# UFBmod_1V1.net
KiCad netlist of a schematic drawn in EAGLE
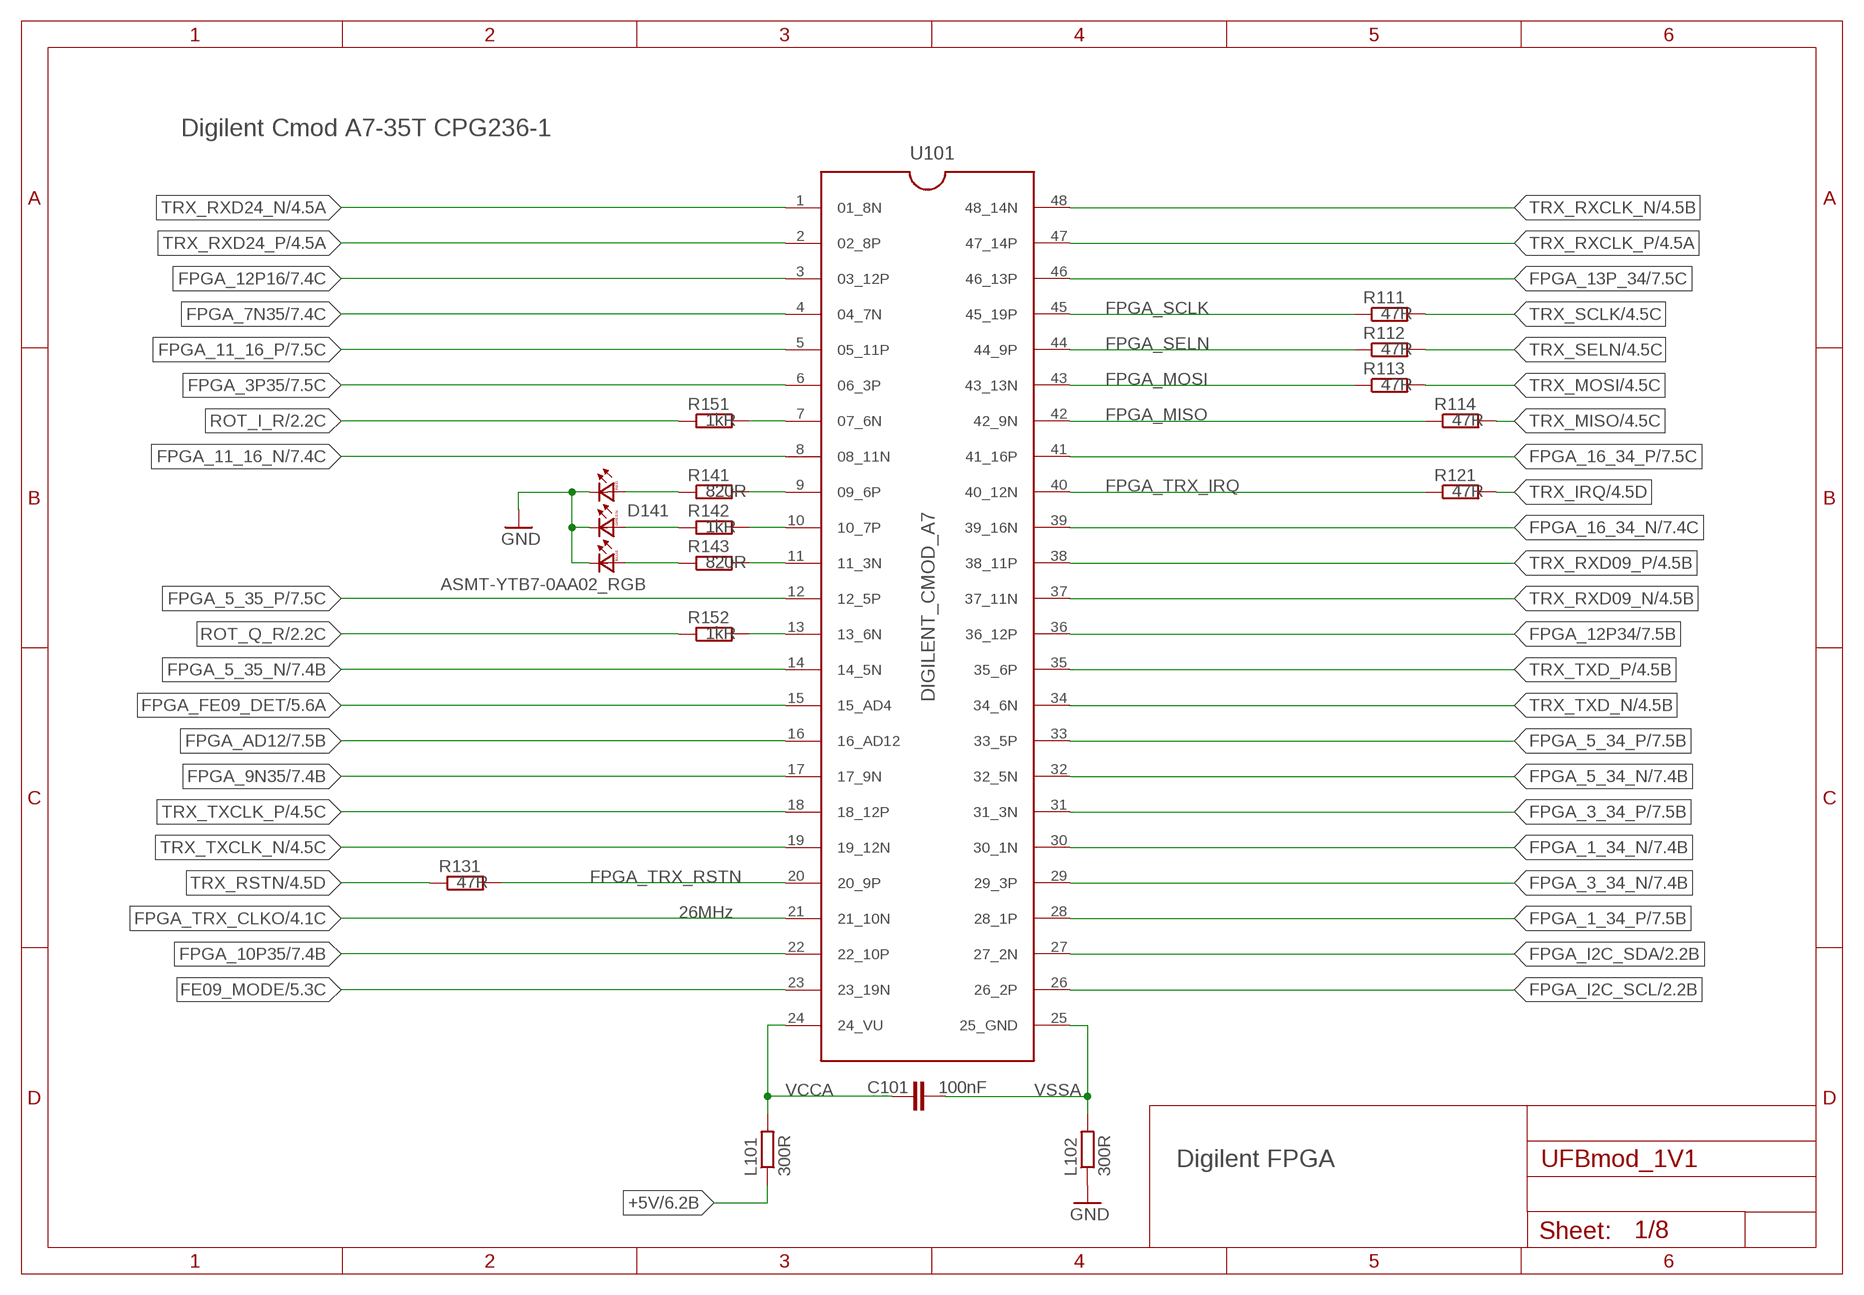
[diagram p0: schematic, sheet 1]
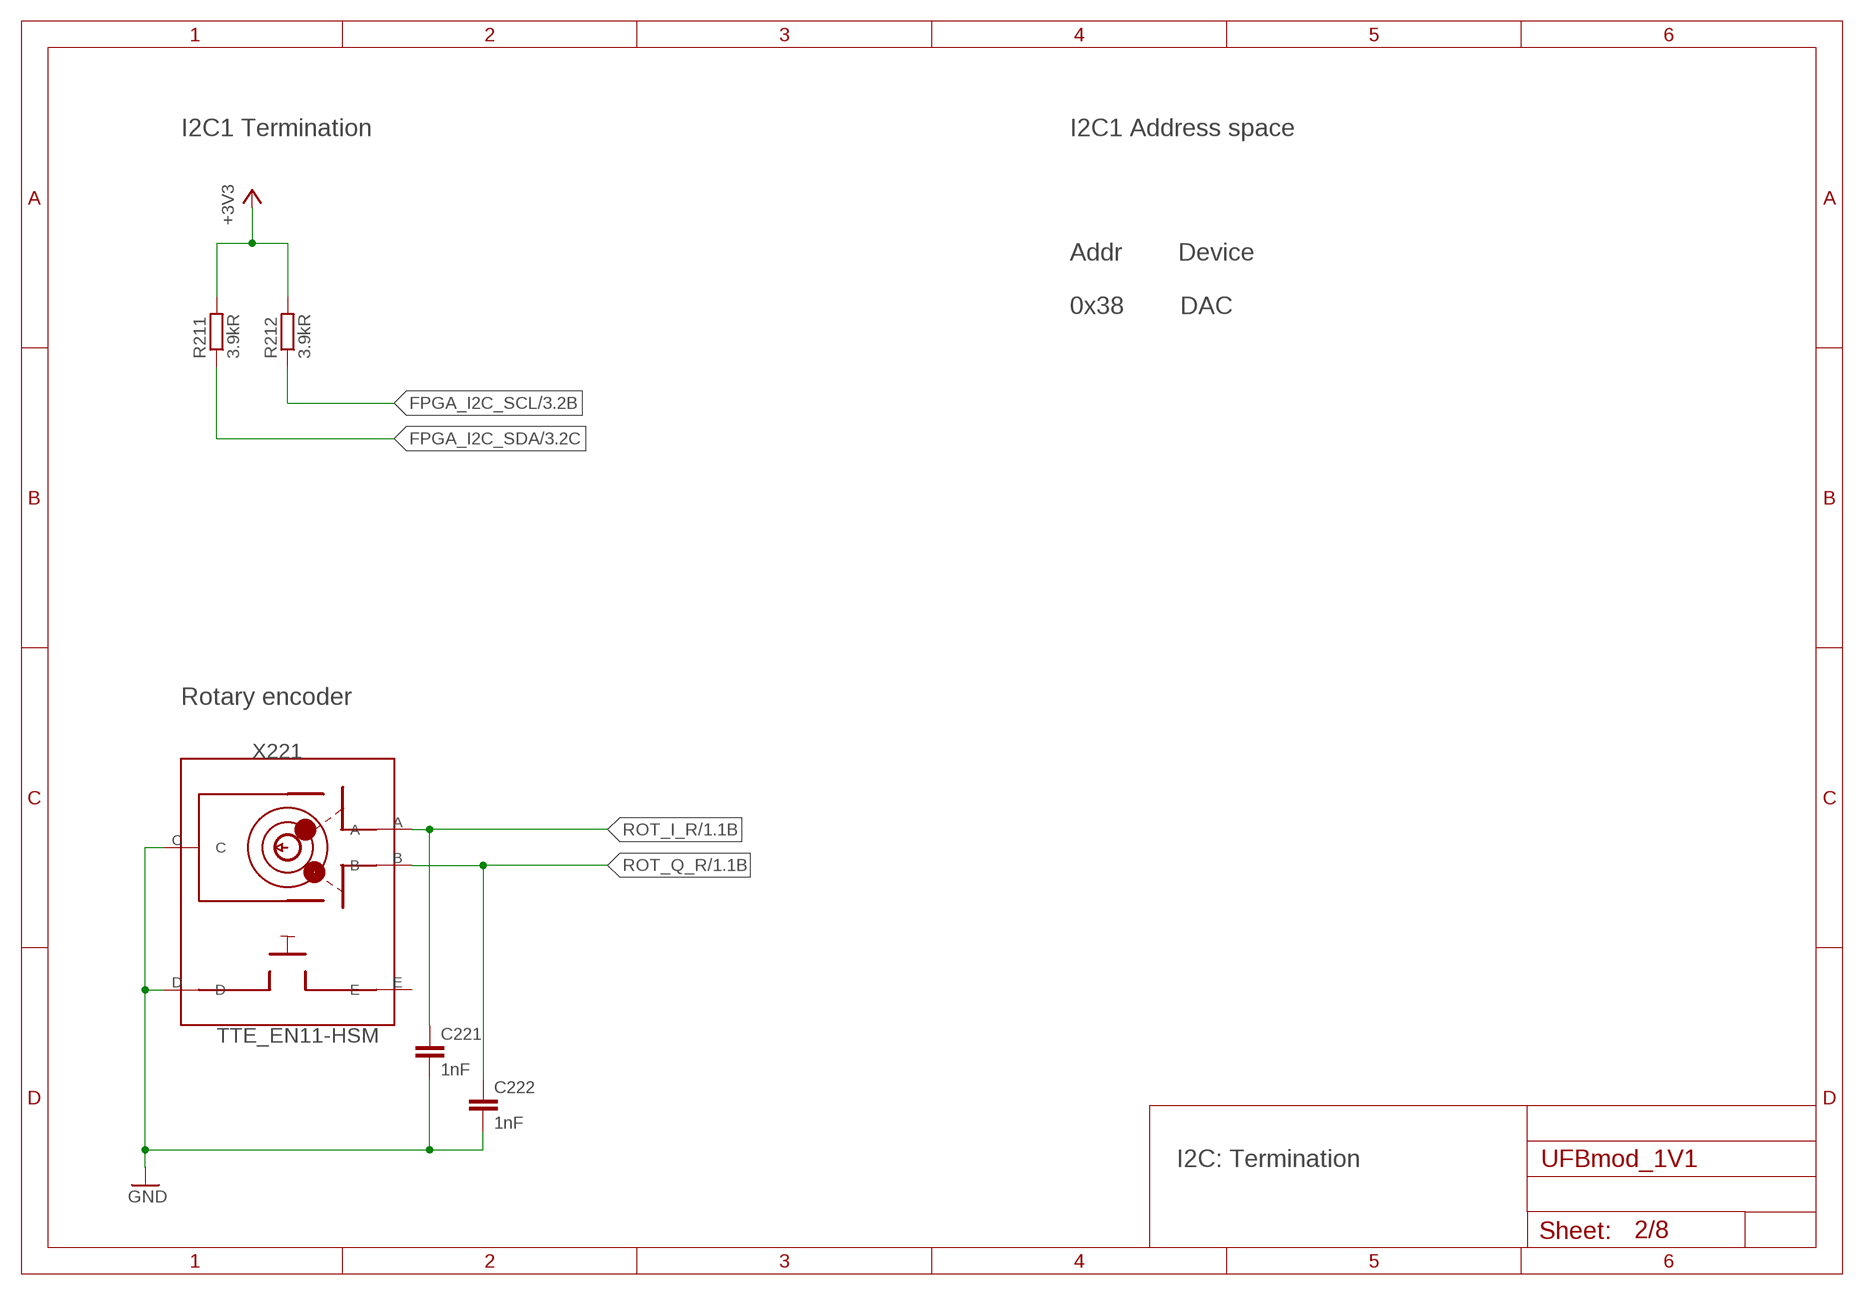
[diagram p1: schematic, sheet 2]
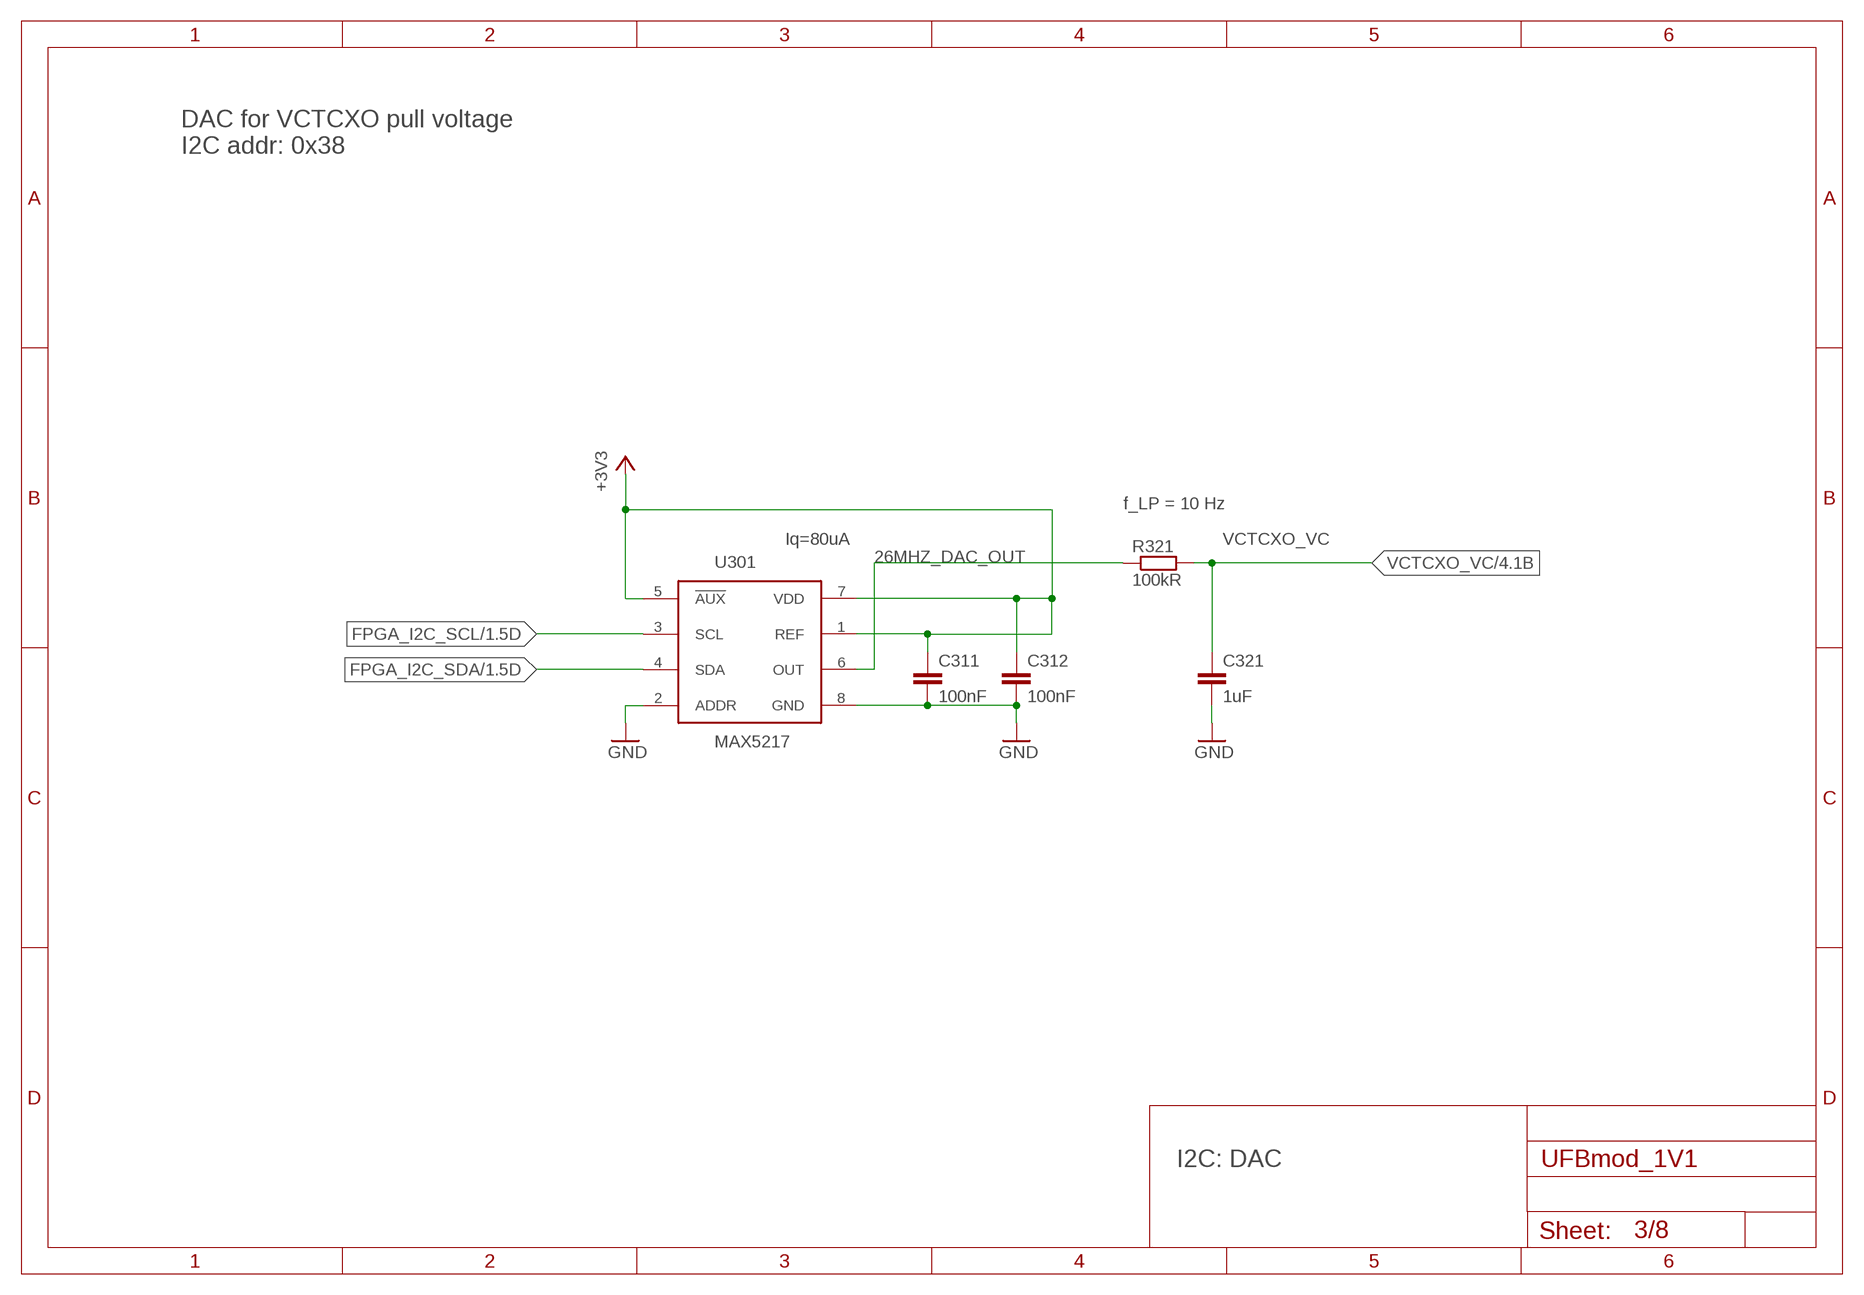
[diagram p2: schematic, sheet 3]
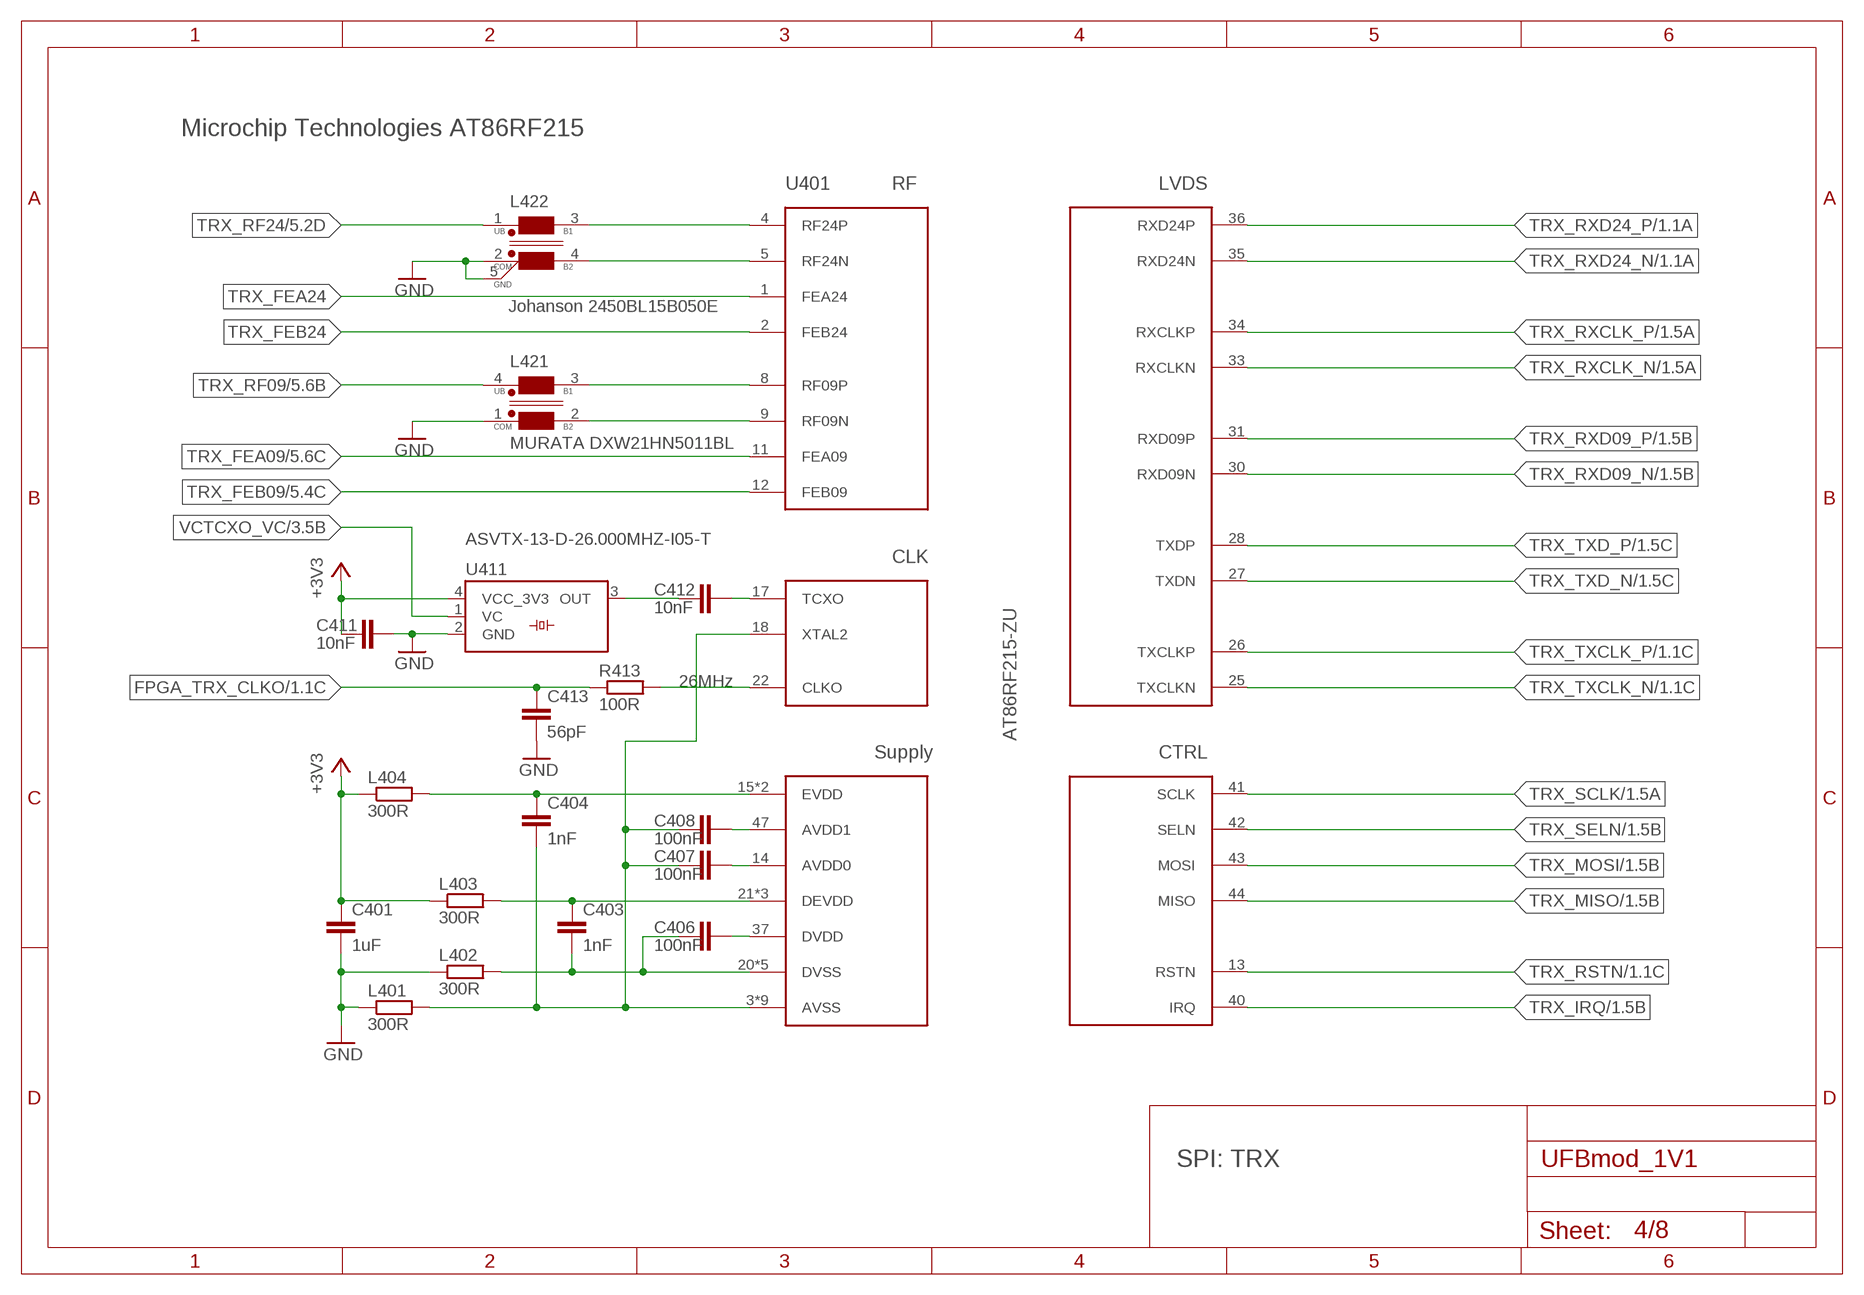
[diagram p3: schematic, sheet 4]
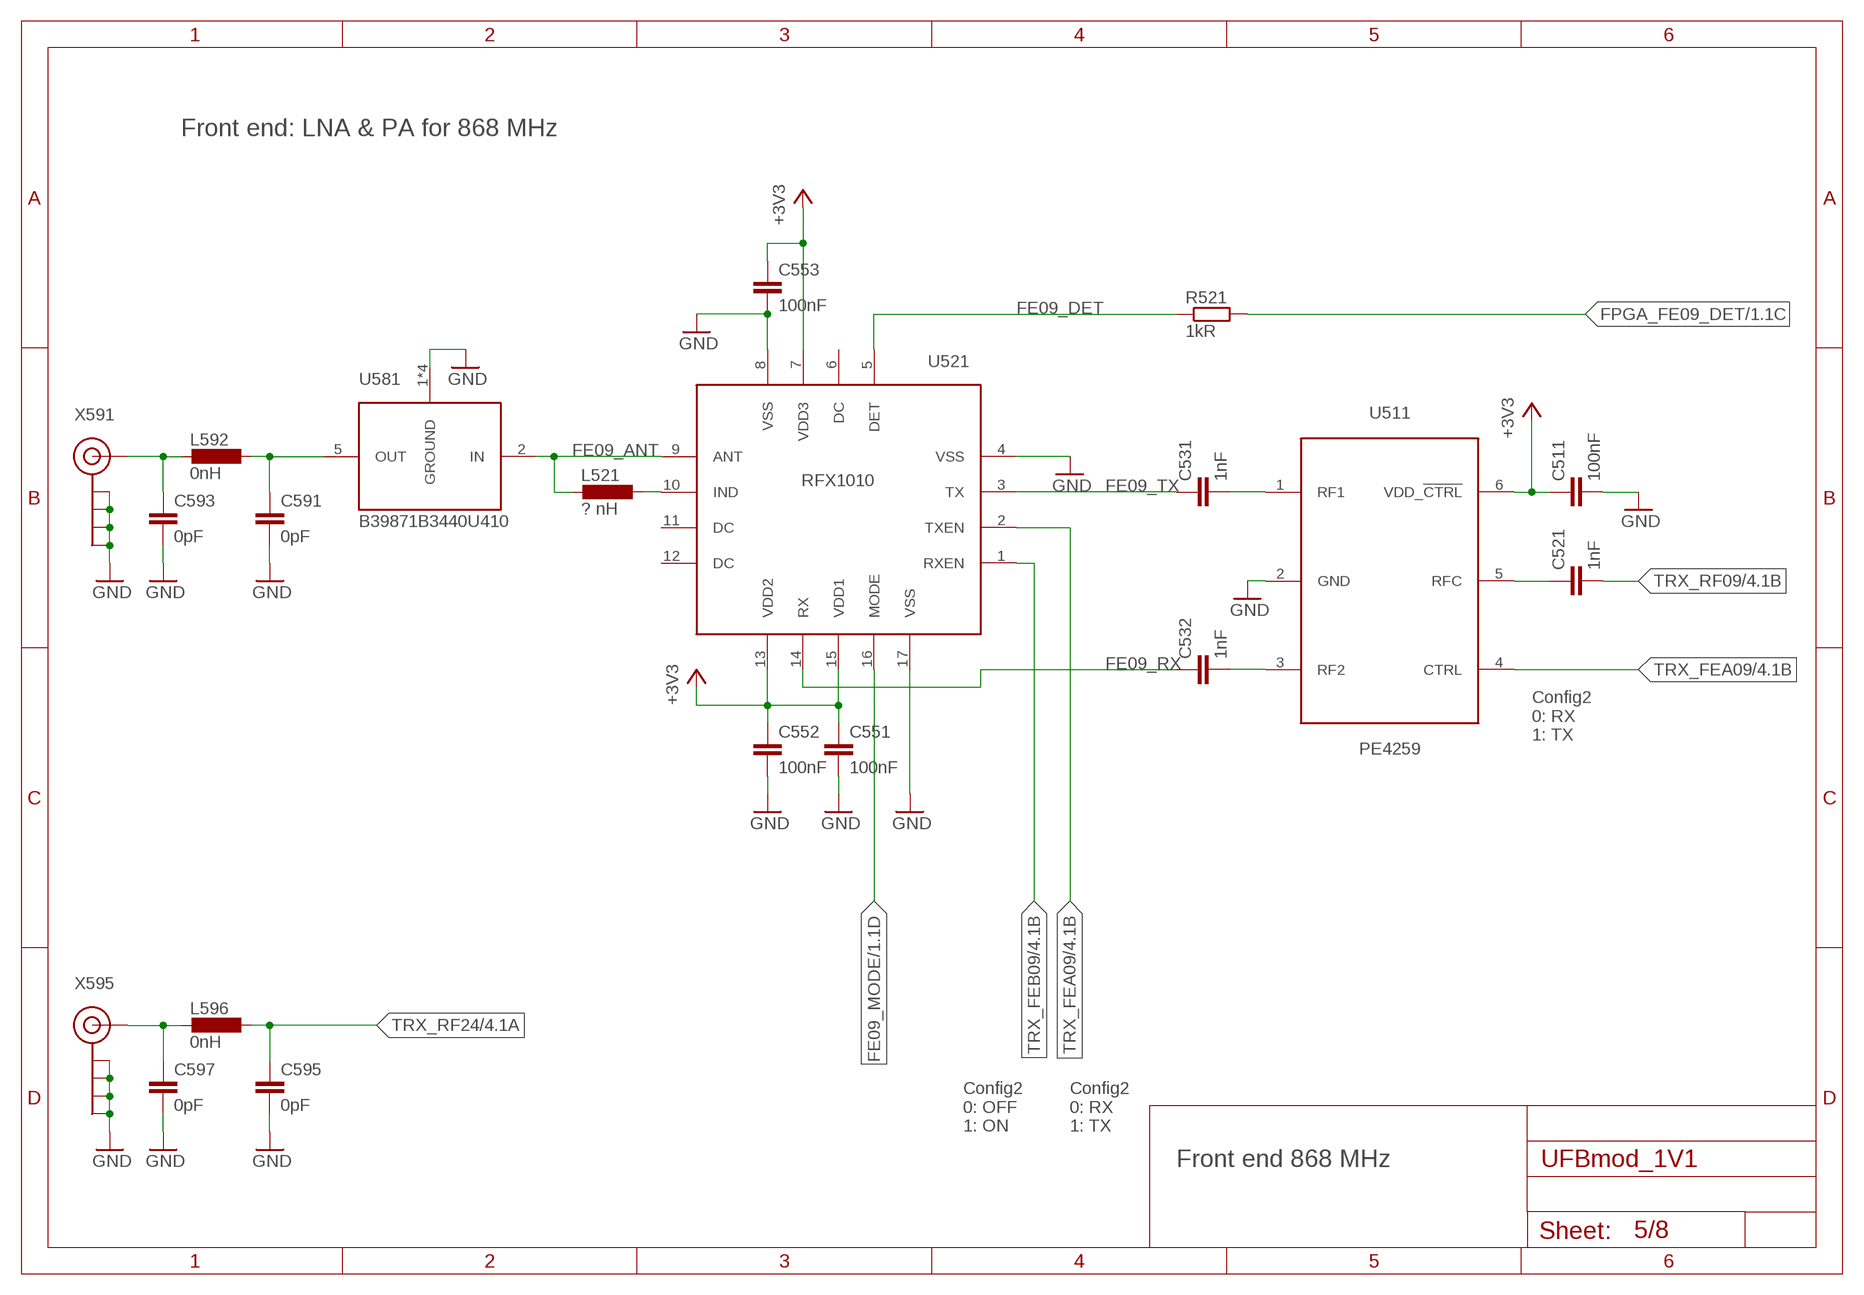
[diagram p4: schematic, sheet 5]
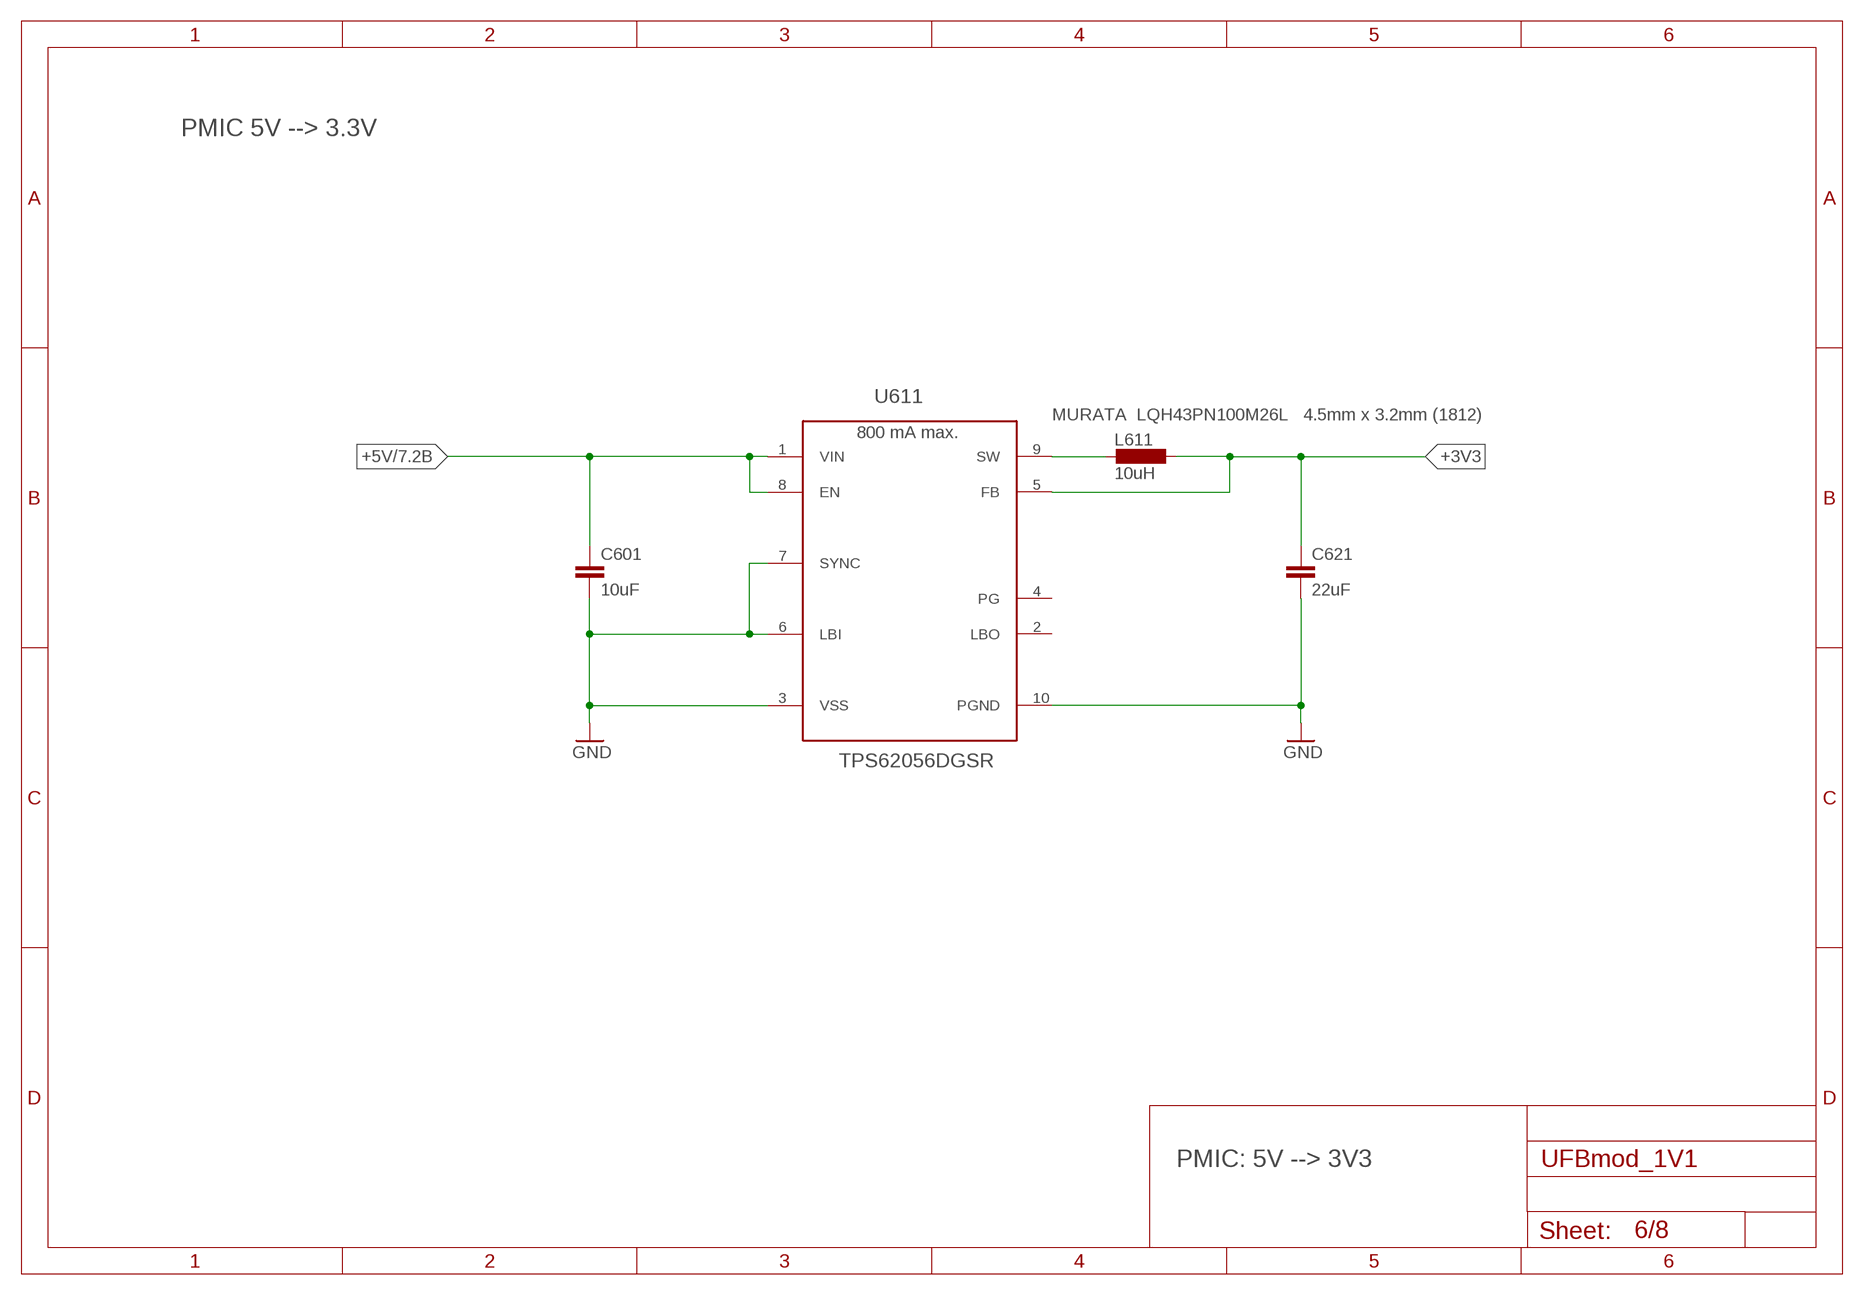
[diagram p5: schematic, sheet 6]
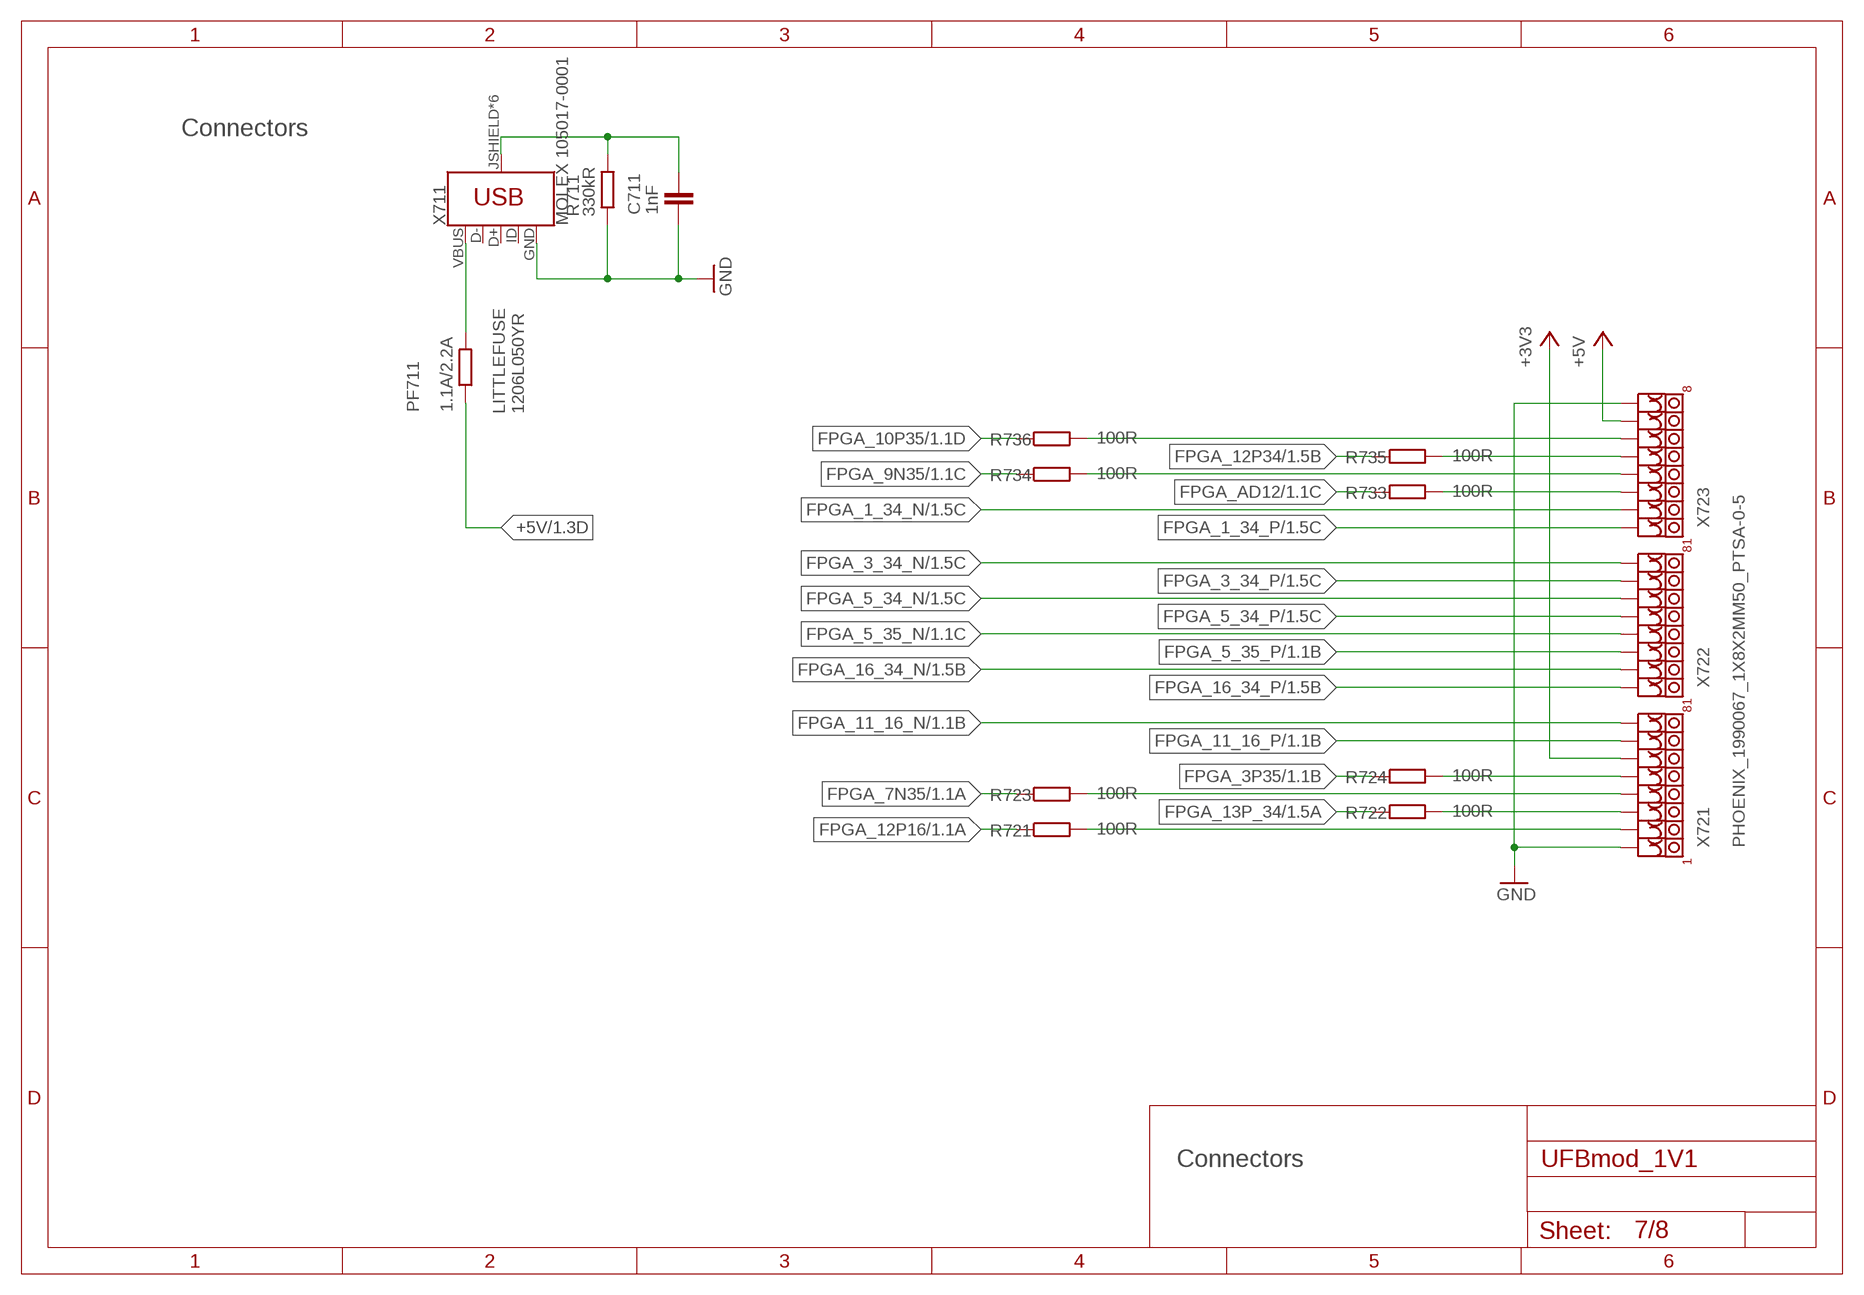
[diagram p6: schematic, sheet 7]
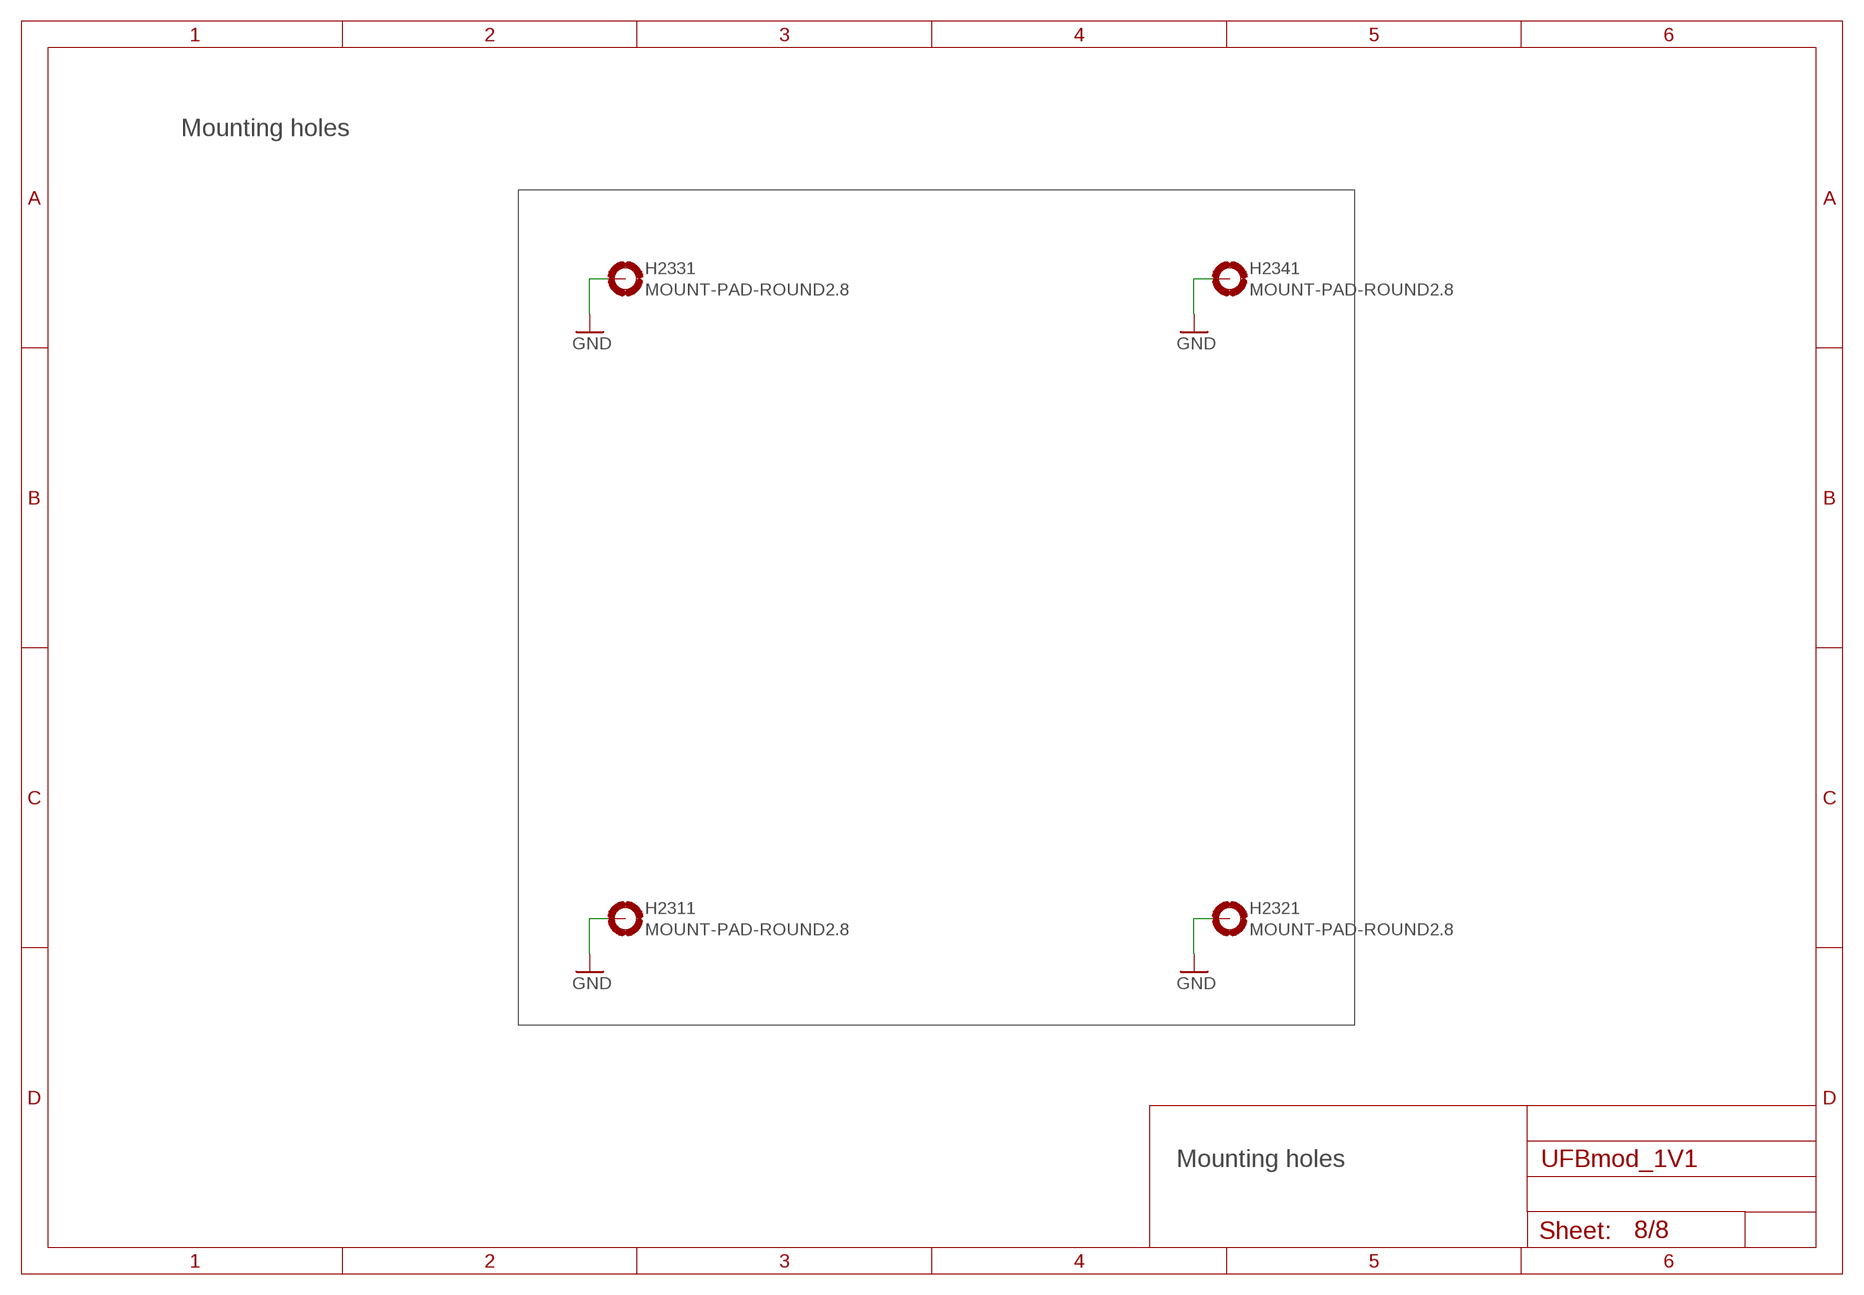
[diagram p7: schematic, sheet 8]

(export (version "E")
  (design (tool "Eeschema 10.0.6"))
  (components
    (comp (ref "C601")
      (value "10uF")
      (footprint "eagle-import:C0603")
      (libsource (lib "eagle-import") (part "C-EUC0603"))
    )
    (comp (ref "C621")
      (value "22uF")
      (footprint "eagle-import:C0603")
      (libsource (lib "eagle-import") (part "C-EUC0603"))
    )
    (comp (ref "L611")
      (value "10uH")
      (footprint "eagle-import:L1812")
      (libsource (lib "eagle-import") (part "L-EUL1812"))
    )
    (comp (ref "U611")
      (value "TPS62056DGSR")
      (footprint "eagle-import:S-PDSO-G10")
      (libsource (lib "eagle-import") (part "TPS62051"))
    )
    (comp (ref "C711")
      (value "1nF")
      (footprint "eagle-import:C0402")
      (libsource (lib "eagle-import") (part "C-EUC0402"))
    )
    (comp (ref "PF711")
      (value "1.1A/2.2A")
      (footprint "eagle-import:M1206")
      (libsource (lib "eagle-import") (part "rcl_R-EU_M1206"))
    )
    (comp (ref "R711")
      (value "330kR")
      (footprint "eagle-import:R0402")
      (libsource (lib "eagle-import") (part "R-EU_R0402"))
    )
    (comp (ref "R721")
      (value "100R")
      (footprint "eagle-import:R0402")
      (libsource (lib "eagle-import") (part "R-EU_R0402"))
    )
    (comp (ref "R722")
      (value "100R")
      (footprint "eagle-import:R0402")
      (libsource (lib "eagle-import") (part "R-EU_R0402"))
    )
    (comp (ref "R723")
      (value "100R")
      (footprint "eagle-import:R0402")
      (libsource (lib "eagle-import") (part "R-EU_R0402"))
    )
    (comp (ref "R724")
      (value "100R")
      (footprint "eagle-import:R0402")
      (libsource (lib "eagle-import") (part "R-EU_R0402"))
    )
    (comp (ref "R733")
      (value "100R")
      (footprint "eagle-import:R0402")
      (libsource (lib "eagle-import") (part "R-EU_R0402"))
    )
    (comp (ref "R734")
      (value "100R")
      (footprint "eagle-import:R0402")
      (libsource (lib "eagle-import") (part "R-EU_R0402"))
    )
    (comp (ref "R735")
      (value "100R")
      (footprint "eagle-import:R0402")
      (libsource (lib "eagle-import") (part "R-EU_R0402"))
    )
    (comp (ref "R736")
      (value "100R")
      (footprint "eagle-import:R0402")
      (libsource (lib "eagle-import") (part "R-EU_R0402"))
    )
    (comp (ref "X711")
      (value "MOLEX 105017-0001")
      (footprint "eagle-import:USB-B-MICRO-SMD_MOLEX-105017-0001")
      (libsource (lib "eagle-import") (part "USB_MICRO-B_MOLEX"))
    )
    (comp (ref "X721")
      (value "PHOENIX_1990067_1X8X2MM50_PTSA-0-5")
      (footprint "eagle-import:PHOENIX_1990067_1X8X2MM50_PTSA-0-5")
      (libsource (lib "eagle-import") (part "PHOENIX_1990067_1X8X2MM50_PTSA-0-5"))
    )
    (comp (ref "X722")
      (value "PHOENIX_1990067_1X8X2MM50_PTSA-0-5")
      (footprint "eagle-import:PHOENIX_1990067_1X8X2MM50_PTSA-0-5")
      (libsource (lib "eagle-import") (part "PHOENIX_1990067_1X8X2MM50_PTSA-0-5"))
    )
    (comp (ref "X723")
      (value "PHOENIX_1990067_1X8X2MM50_PTSA-0-5")
      (footprint "eagle-import:PHOENIX_1990067_1X8X2MM50_PTSA-0-5")
      (libsource (lib "eagle-import") (part "PHOENIX_1990067_1X8X2MM50_PTSA-0-5"))
    )
    (comp (ref "C511")
      (value "100nF")
      (footprint "eagle-import:C0402")
      (libsource (lib "eagle-import") (part "C-EUC0402"))
    )
    (comp (ref "C521")
      (value "1nF")
      (footprint "eagle-import:C0402")
      (libsource (lib "eagle-import") (part "C-EUC0402"))
    )
    (comp (ref "C531")
      (value "1nF")
      (footprint "eagle-import:C0402")
      (libsource (lib "eagle-import") (part "C-EUC0402"))
    )
    (comp (ref "C532")
      (value "1nF")
      (footprint "eagle-import:C0402")
      (libsource (lib "eagle-import") (part "C-EUC0402"))
    )
    (comp (ref "C551")
      (value "100nF")
      (footprint "eagle-import:C0402")
      (libsource (lib "eagle-import") (part "C-EUC0402"))
    )
    (comp (ref "C552")
      (value "100nF")
      (footprint "eagle-import:C0402")
      (libsource (lib "eagle-import") (part "C-EUC0402"))
    )
    (comp (ref "C553")
      (value "100nF")
      (footprint "eagle-import:C0402")
      (libsource (lib "eagle-import") (part "C-EUC0402"))
    )
    (comp (ref "C591")
      (value "0pF")
      (footprint "eagle-import:C0402")
      (libsource (lib "eagle-import") (part "C-EUC0402"))
    )
    (comp (ref "C593")
      (value "0pF")
      (footprint "eagle-import:C0402")
      (libsource (lib "eagle-import") (part "C-EUC0402"))
    )
    (comp (ref "C595")
      (value "0pF")
      (footprint "eagle-import:C0402")
      (libsource (lib "eagle-import") (part "C-EUC0402"))
    )
    (comp (ref "C597")
      (value "0pF")
      (footprint "eagle-import:C0402")
      (libsource (lib "eagle-import") (part "C-EUC0402"))
    )
    (comp (ref "L521")
      (value "? nH")
      (footprint "eagle-import:L0603")
      (libsource (lib "eagle-import") (part "L-EUL0603"))
    )
    (comp (ref "L592")
      (value "0nH")
      (footprint "eagle-import:L0603")
      (libsource (lib "eagle-import") (part "L-EUL0603"))
    )
    (comp (ref "L596")
      (value "0nH")
      (footprint "eagle-import:L0603")
      (libsource (lib "eagle-import") (part "L-EUL0603"))
    )
    (comp (ref "R521")
      (value "1kR")
      (footprint "eagle-import:R0402")
      (libsource (lib "eagle-import") (part "R-EU_R0402"))
    )
    (comp (ref "U511")
      (value "PE4259")
      (footprint "eagle-import:SC-70_6-LEAD_2X1MM25_0P65")
      (libsource (lib "eagle-import") (part "PE4259"))
    )
    (comp (ref "U521")
      (value "RFX1010")
      (footprint "eagle-import:QFN16-3X3-0P5-PAD")
      (libsource (lib "eagle-import") (part "RFX1010"))
    )
    (comp (ref "U581")
      (value "B39871B3440U410")
      (footprint "eagle-import:B3440_3MM-X-3MM")
      (libsource (lib "eagle-import") (part "B3440"))
    )
    (comp (ref "X591")
      (value "ANTENNATINY")
      (footprint "eagle-import:SMA_UFL_PAD_TINY")
      (libsource (lib "eagle-import") (part "ANTENNATINY"))
    )
    (comp (ref "X595")
      (value "ANTENNATINY")
      (footprint "eagle-import:SMA_UFL_PAD_TINY")
      (libsource (lib "eagle-import") (part "ANTENNATINY"))
    )
    (comp (ref "C311")
      (value "100nF")
      (footprint "eagle-import:C0402")
      (libsource (lib "eagle-import") (part "C-EUC0402"))
    )
    (comp (ref "C312")
      (value "100nF")
      (footprint "eagle-import:C0402")
      (libsource (lib "eagle-import") (part "C-EUC0402"))
    )
    (comp (ref "C321")
      (value "1uF")
      (footprint "eagle-import:C0402")
      (libsource (lib "eagle-import") (part "C-EUC0402"))
    )
    (comp (ref "R321")
      (value "100kR")
      (footprint "eagle-import:R0402")
      (libsource (lib "eagle-import") (part "R-EU_R0402"))
    )
    (comp (ref "U301")
      (value "MAX5217")
      (footprint "eagle-import:µMAX8")
      (libsource (lib "eagle-import") (part "MAX5217"))
    )
    (comp (ref "H2311")
      (value "MOUNT-PAD-ROUND2.8")
      (footprint "eagle-import:2,8-PAD")
      (libsource (lib "eagle-import") (part "MOUNT-PAD-ROUND2.8"))
    )
    (comp (ref "H2321")
      (value "MOUNT-PAD-ROUND2.8")
      (footprint "eagle-import:2,8-PAD")
      (libsource (lib "eagle-import") (part "MOUNT-PAD-ROUND2.8"))
    )
    (comp (ref "H2331")
      (value "MOUNT-PAD-ROUND2.8")
      (footprint "eagle-import:2,8-PAD")
      (libsource (lib "eagle-import") (part "MOUNT-PAD-ROUND2.8"))
    )
    (comp (ref "H2341")
      (value "MOUNT-PAD-ROUND2.8")
      (footprint "eagle-import:2,8-PAD")
      (libsource (lib "eagle-import") (part "MOUNT-PAD-ROUND2.8"))
    )
    (comp (ref "C401")
      (value "1uF")
      (footprint "eagle-import:C0402")
      (libsource (lib "eagle-import") (part "C-EUC0402"))
    )
    (comp (ref "C403")
      (value "1nF")
      (footprint "eagle-import:C0402")
      (libsource (lib "eagle-import") (part "C-EUC0402"))
    )
    (comp (ref "C404")
      (value "1nF")
      (footprint "eagle-import:C0402")
      (libsource (lib "eagle-import") (part "C-EUC0402"))
    )
    (comp (ref "C406")
      (value "100nF")
      (footprint "eagle-import:C0402")
      (libsource (lib "eagle-import") (part "C-EUC0402"))
    )
    (comp (ref "C407")
      (value "100nF")
      (footprint "eagle-import:C0402")
      (libsource (lib "eagle-import") (part "C-EUC0402"))
    )
    (comp (ref "C408")
      (value "100nF")
      (footprint "eagle-import:C0402")
      (libsource (lib "eagle-import") (part "C-EUC0402"))
    )
    (comp (ref "C411")
      (value "10nF")
      (footprint "eagle-import:C0402")
      (libsource (lib "eagle-import") (part "C-EUC0402"))
    )
    (comp (ref "C412")
      (value "10nF")
      (footprint "eagle-import:C0402")
      (libsource (lib "eagle-import") (part "C-EUC0402"))
    )
    (comp (ref "C413")
      (value "56pF")
      (footprint "eagle-import:C0402")
      (libsource (lib "eagle-import") (part "C-EUC0402"))
    )
    (comp (ref "L401")
      (value "300R")
      (footprint "eagle-import:R1206")
      (libsource (lib "eagle-import") (part "R-EU_R1206"))
    )
    (comp (ref "L402")
      (value "300R")
      (footprint "eagle-import:R1206")
      (libsource (lib "eagle-import") (part "R-EU_R1206"))
    )
    (comp (ref "L403")
      (value "300R")
      (footprint "eagle-import:R1206")
      (libsource (lib "eagle-import") (part "R-EU_R1206"))
    )
    (comp (ref "L404")
      (value "300R")
      (footprint "eagle-import:R1206")
      (libsource (lib "eagle-import") (part "R-EU_R1206"))
    )
    (comp (ref "L421")
      (value "MURATA DXW21HN5011BL")
      (footprint "eagle-import:DXW21HN5011BL")
      (libsource (lib "eagle-import") (part "DXW21HN5011BL"))
    )
    (comp (ref "L422")
      (value "Johanson 2450BL15B050E")
      (footprint "eagle-import:2450BL15B050")
      (libsource (lib "eagle-import") (part "2450BL15B050"))
    )
    (comp (ref "R413")
      (value "100R")
      (footprint "eagle-import:R0402")
      (libsource (lib "eagle-import") (part "R-EU_R0402"))
    )
    (comp (ref "U401")
      (value "AT86RF215-ZU")
      (footprint "eagle-import:QFN48_7X7-0P5-PAD")
      (libsource (lib "eagle-import") (part "AT86RF215"))
    )
    (comp (ref "U411")
      (value "ASVTX-13-D-26.000MHZ-I05-T")
      (footprint "eagle-import:ASVTX-13")
      (libsource (lib "eagle-import") (part "ASVTX-13-D"))
    )
    (comp (ref "C101")
      (value "100nF")
      (footprint "eagle-import:C0402")
      (libsource (lib "eagle-import") (part "C-EUC0402"))
    )
    (comp (ref "D141")
      (value "ASMT-YTB7-0AA02_RGB")
      (footprint "eagle-import:ASMT-YTB7_0AA02_RGB")
      (libsource (lib "eagle-import") (part "ASMT-YTB7-0AA02_RGB"))
    )
    (comp (ref "L101")
      (value "300R")
      (footprint "eagle-import:R1206")
      (libsource (lib "eagle-import") (part "R-EU_R1206"))
    )
    (comp (ref "L102")
      (value "300R")
      (footprint "eagle-import:R1206")
      (libsource (lib "eagle-import") (part "R-EU_R1206"))
    )
    (comp (ref "R111")
      (value "47R")
      (footprint "eagle-import:R0402")
      (libsource (lib "eagle-import") (part "R-EU_R0402"))
    )
    (comp (ref "R112")
      (value "47R")
      (footprint "eagle-import:R0402")
      (libsource (lib "eagle-import") (part "R-EU_R0402"))
    )
    (comp (ref "R113")
      (value "47R")
      (footprint "eagle-import:R0402")
      (libsource (lib "eagle-import") (part "R-EU_R0402"))
    )
    (comp (ref "R114")
      (value "47R")
      (footprint "eagle-import:R0402")
      (libsource (lib "eagle-import") (part "R-EU_R0402"))
    )
    (comp (ref "R121")
      (value "47R")
      (footprint "eagle-import:R0402")
      (libsource (lib "eagle-import") (part "R-EU_R0402"))
    )
    (comp (ref "R131")
      (value "47R")
      (footprint "eagle-import:R0402")
      (libsource (lib "eagle-import") (part "R-EU_R0402"))
    )
    (comp (ref "R141")
      (value "820R")
      (footprint "eagle-import:R0402")
      (libsource (lib "eagle-import") (part "R-EU_R0402"))
    )
    (comp (ref "R142")
      (value "1kR")
      (footprint "eagle-import:R0402")
      (libsource (lib "eagle-import") (part "R-EU_R0402"))
    )
    (comp (ref "R143")
      (value "820R")
      (footprint "eagle-import:R0402")
      (libsource (lib "eagle-import") (part "R-EU_R0402"))
    )
    (comp (ref "R151")
      (value "1kR")
      (footprint "eagle-import:R0402")
      (libsource (lib "eagle-import") (part "R-EU_R0402"))
    )
    (comp (ref "R152")
      (value "1kR")
      (footprint "eagle-import:R0402")
      (libsource (lib "eagle-import") (part "R-EU_R0402"))
    )
    (comp (ref "U101")
      (value "DIGILENT_CMOD_A7")
      (footprint "eagle-import:DIGILENT_CMOD_A7__DIP48")
      (libsource (lib "eagle-import") (part "DIGILENT_CMOD_A7"))
    )
    (comp (ref "C221")
      (value "1nF")
      (footprint "eagle-import:C0402")
      (libsource (lib "eagle-import") (part "C-EUC0402"))
    )
    (comp (ref "C222")
      (value "1nF")
      (footprint "eagle-import:C0402")
      (libsource (lib "eagle-import") (part "C-EUC0402"))
    )
    (comp (ref "R211")
      (value "3.9kR")
      (footprint "eagle-import:R0402")
      (libsource (lib "eagle-import") (part "R-EU_R0402"))
    )
    (comp (ref "R212")
      (value "3.9kR")
      (footprint "eagle-import:R0402")
      (libsource (lib "eagle-import") (part "R-EU_R0402"))
    )
    (comp (ref "X221")
      (value "TTE_EN11-HSM")
      (footprint "eagle-import:TTE_EN11-HSM")
      (libsource (lib "eagle-import") (part "TTE_EN11-HSM"))
    )
  )
  (nets
    (net (code "1") (name "+3V3") (class "Default")
      (node (ref "C311") (pin "1") (pinfunction "1_1") (pintype "passive"))
      (node (ref "C312") (pin "1") (pinfunction "1_1") (pintype "passive"))
      (node (ref "C401") (pin "1") (pinfunction "1_1") (pintype "passive"))
      (node (ref "C411") (pin "1") (pinfunction "1_1") (pintype "passive"))
      (node (ref "C511") (pin "1") (pinfunction "1_1") (pintype "passive"))
      (node (ref "C551") (pin "1") (pinfunction "1_1") (pintype "passive"))
      (node (ref "C552") (pin "1") (pinfunction "1_1") (pintype "passive"))
      (node (ref "C553") (pin "1") (pinfunction "1_1") (pintype "passive"))
      (node (ref "C621") (pin "1") (pinfunction "1_1") (pintype "passive"))
      (node (ref "L403") (pin "1") (pinfunction "1_1") (pintype "passive"))
      (node (ref "L404") (pin "1") (pinfunction "1_1") (pintype "passive"))
      (node (ref "L611") (pin "1") (pinfunction "1_1") (pintype "passive"))
      (node (ref "R211") (pin "2") (pinfunction "2_2") (pintype "passive"))
      (node (ref "R212") (pin "2") (pinfunction "2_2") (pintype "passive"))
      (node (ref "U301") (pin "1") (pinfunction "REF_1") (pintype "passive"))
      (node (ref "U301") (pin "5") (pinfunction "~{AUX}_5") (pintype "input"))
      (node (ref "U301") (pin "7") (pinfunction "VDD_7") (pintype "power_in"))
      (node (ref "U411") (pin "4") (pinfunction "VCC_3V3_4") (pintype "power_in"))
      (node (ref "U511") (pin "6") (pinfunction "VDD_~{CTRL}_6") (pintype "passive"))
      (node (ref "U521") (pin "13") (pinfunction "VDD2_13") (pintype "power_in"))
      (node (ref "U521") (pin "15") (pinfunction "VDD1_15") (pintype "power_in"))
      (node (ref "U521") (pin "7") (pinfunction "VDD3_7") (pintype "power_in"))
      (node (ref "U611") (pin "5") (pinfunction "FB_5") (pintype "passive"))
      (node (ref "X721") (pin "6") (pinfunction "6_6") (pintype "passive"))
    )
    (net (code "2") (name "+5V") (class "Default")
      (node (ref "C601") (pin "1") (pinfunction "1_1") (pintype "passive"))
      (node (ref "L101") (pin "1") (pinfunction "1_1") (pintype "passive"))
      (node (ref "PF711") (pin "1") (pinfunction "1_1") (pintype "passive"))
      (node (ref "U611") (pin "1") (pinfunction "VIN_1") (pintype "power_in"))
      (node (ref "U611") (pin "8") (pinfunction "EN_8") (pintype "input"))
      (node (ref "X723") (pin "7") (pinfunction "7_7") (pintype "passive"))
    )
    (net (code "3") (name "26MHZ_DAC_OUT") (class "Default")
      (node (ref "R321") (pin "1") (pinfunction "1_1") (pintype "passive"))
      (node (ref "U301") (pin "6") (pinfunction "OUT_6") (pintype "passive"))
    )
    (net (code "4") (name "FE09_ANT") (class "Default")
      (node (ref "L521") (pin "2") (pinfunction "2_2") (pintype "passive"))
      (node (ref "U521") (pin "9") (pinfunction "ANT_9") (pintype "bidirectional"))
      (node (ref "U581") (pin "2") (pinfunction "IN_2") (pintype "passive"))
    )
    (net (code "5") (name "FE09_DET") (class "Default")
      (node (ref "R521") (pin "1") (pinfunction "1_1") (pintype "passive"))
      (node (ref "U521") (pin "5") (pinfunction "DET_5") (pintype "output"))
    )
    (net (code "6") (name "FE09_MODE") (class "Default")
      (node (ref "U101") (pin "23") (pinfunction "23_19N_23") (pintype "bidirectional"))
      (node (ref "U521") (pin "16") (pinfunction "MODE_16") (pintype "input"))
    )
    (net (code "7") (name "FE09_RX") (class "Default")
      (node (ref "C532") (pin "1") (pinfunction "1_1") (pintype "passive"))
      (node (ref "U521") (pin "14") (pinfunction "RX_14") (pintype "output"))
    )
    (net (code "8") (name "FE09_TX") (class "Default")
      (node (ref "C531") (pin "1") (pinfunction "1_1") (pintype "passive"))
      (node (ref "U521") (pin "3") (pinfunction "TX_3") (pintype "input"))
    )
    (net (code "9") (name "FPGA_1_34_N") (class "Default")
      (node (ref "U101") (pin "30") (pinfunction "30_1N_30") (pintype "bidirectional"))
      (node (ref "X723") (pin "2") (pinfunction "2_2") (pintype "passive"))
    )
    (net (code "10") (name "FPGA_1_34_P") (class "Default")
      (node (ref "U101") (pin "28") (pinfunction "28_1P_28") (pintype "bidirectional"))
      (node (ref "X723") (pin "1") (pinfunction "1_1") (pintype "passive"))
    )
    (net (code "11") (name "FPGA_3P35") (class "Default")
      (node (ref "R724") (pin "1") (pinfunction "1_1") (pintype "passive"))
      (node (ref "U101") (pin "6") (pinfunction "06_3P_6") (pintype "bidirectional"))
    )
    (net (code "12") (name "FPGA_3_34_N") (class "Default")
      (node (ref "U101") (pin "29") (pinfunction "29_3P_29") (pintype "bidirectional"))
      (node (ref "X722") (pin "8") (pinfunction "8_8") (pintype "passive"))
    )
    (net (code "13") (name "FPGA_3_34_P") (class "Default")
      (node (ref "U101") (pin "31") (pinfunction "31_3N_31") (pintype "bidirectional"))
      (node (ref "X722") (pin "7") (pinfunction "7_7") (pintype "passive"))
    )
    (net (code "14") (name "FPGA_5_34_N") (class "Default")
      (node (ref "U101") (pin "32") (pinfunction "32_5N_32") (pintype "bidirectional"))
      (node (ref "X722") (pin "6") (pinfunction "6_6") (pintype "passive"))
    )
    (net (code "15") (name "FPGA_5_34_P") (class "Default")
      (node (ref "U101") (pin "33") (pinfunction "33_5P_33") (pintype "bidirectional"))
      (node (ref "X722") (pin "5") (pinfunction "5_5") (pintype "passive"))
    )
    (net (code "16") (name "FPGA_5_35_N") (class "Default")
      (node (ref "U101") (pin "14") (pinfunction "14_5N_14") (pintype "bidirectional"))
      (node (ref "X722") (pin "4") (pinfunction "4_4") (pintype "passive"))
    )
    (net (code "17") (name "FPGA_5_35_P") (class "Default")
      (node (ref "U101") (pin "12") (pinfunction "12_5P_12") (pintype "bidirectional"))
      (node (ref "X722") (pin "3") (pinfunction "3_3") (pintype "passive"))
    )
    (net (code "18") (name "FPGA_7N35") (class "Default")
      (node (ref "R723") (pin "1") (pinfunction "1_1") (pintype "passive"))
      (node (ref "U101") (pin "4") (pinfunction "04_7N_4") (pintype "bidirectional"))
    )
    (net (code "19") (name "FPGA_9N35") (class "Default")
      (node (ref "R734") (pin "1") (pinfunction "1_1") (pintype "passive"))
      (node (ref "U101") (pin "17") (pinfunction "17_9N_17") (pintype "bidirectional"))
    )
    (net (code "20") (name "FPGA_10P35") (class "Default")
      (node (ref "R736") (pin "1") (pinfunction "1_1") (pintype "passive"))
      (node (ref "U101") (pin "22") (pinfunction "22_10P_22") (pintype "bidirectional"))
    )
    (net (code "21") (name "FPGA_11_16_N") (class "Default")
      (node (ref "U101") (pin "8") (pinfunction "08_11N_8") (pintype "bidirectional"))
      (node (ref "X721") (pin "8") (pinfunction "8_8") (pintype "passive"))
    )
    (net (code "22") (name "FPGA_11_16_P") (class "Default")
      (node (ref "U101") (pin "5") (pinfunction "05_11P_5") (pintype "bidirectional"))
      (node (ref "X721") (pin "7") (pinfunction "7_7") (pintype "passive"))
    )
    (net (code "23") (name "FPGA_12P16") (class "Default")
      (node (ref "R721") (pin "1") (pinfunction "1_1") (pintype "passive"))
      (node (ref "U101") (pin "3") (pinfunction "03_12P_3") (pintype "bidirectional"))
    )
    (net (code "24") (name "FPGA_12P34") (class "Default")
      (node (ref "R735") (pin "1") (pinfunction "1_1") (pintype "passive"))
      (node (ref "U101") (pin "36") (pinfunction "36_12P_36") (pintype "bidirectional"))
    )
    (net (code "25") (name "FPGA_13P_34") (class "Default")
      (node (ref "R722") (pin "1") (pinfunction "1_1") (pintype "passive"))
      (node (ref "U101") (pin "46") (pinfunction "46_13P_46") (pintype "bidirectional"))
    )
    (net (code "26") (name "FPGA_16_34_N") (class "Default")
      (node (ref "U101") (pin "39") (pinfunction "39_16N_39") (pintype "bidirectional"))
      (node (ref "X722") (pin "2") (pinfunction "2_2") (pintype "passive"))
    )
    (net (code "27") (name "FPGA_16_34_P") (class "Default")
      (node (ref "U101") (pin "41") (pinfunction "41_16P_41") (pintype "bidirectional"))
      (node (ref "X722") (pin "1") (pinfunction "1_1") (pintype "passive"))
    )
    (net (code "28") (name "FPGA_AD12") (class "Default")
      (node (ref "R733") (pin "1") (pinfunction "1_1") (pintype "passive"))
      (node (ref "U101") (pin "16") (pinfunction "16_AD12_16") (pintype "bidirectional"))
    )
    (net (code "29") (name "FPGA_FE09_DET") (class "Default")
      (node (ref "R521") (pin "2") (pinfunction "2_2") (pintype "passive"))
      (node (ref "U101") (pin "15") (pinfunction "15_AD4_15") (pintype "bidirectional"))
    )
    (net (code "30") (name "FPGA_I2C_SCL") (class "Default")
      (node (ref "R212") (pin "1") (pinfunction "1_1") (pintype "passive"))
      (node (ref "U101") (pin "26") (pinfunction "26_2P_26") (pintype "bidirectional"))
      (node (ref "U301") (pin "3") (pinfunction "SCL_3") (pintype "input"))
    )
    (net (code "31") (name "FPGA_I2C_SDA") (class "Default")
      (node (ref "R211") (pin "1") (pinfunction "1_1") (pintype "passive"))
      (node (ref "U101") (pin "27") (pinfunction "27_2N_27") (pintype "bidirectional"))
      (node (ref "U301") (pin "4") (pinfunction "SDA_4") (pintype "tri_state"))
    )
    (net (code "32") (name "FPGA_MISO") (class "Default")
      (node (ref "R114") (pin "1") (pinfunction "1_1") (pintype "passive"))
      (node (ref "U101") (pin "42") (pinfunction "42_9N_42") (pintype "bidirectional"))
    )
    (net (code "33") (name "FPGA_MOSI") (class "Default")
      (node (ref "R113") (pin "1") (pinfunction "1_1") (pintype "passive"))
      (node (ref "U101") (pin "43") (pinfunction "43_13N_43") (pintype "bidirectional"))
    )
    (net (code "34") (name "FPGA_SCLK") (class "Default")
      (node (ref "R111") (pin "1") (pinfunction "1_1") (pintype "passive"))
      (node (ref "U101") (pin "45") (pinfunction "45_19P_45") (pintype "bidirectional"))
    )
    (net (code "35") (name "FPGA_SELN") (class "Default")
      (node (ref "R112") (pin "1") (pinfunction "1_1") (pintype "passive"))
      (node (ref "U101") (pin "44") (pinfunction "44_9P_44") (pintype "bidirectional"))
    )
    (net (code "36") (name "FPGA_TRX_CLKO") (class "Default")
      (node (ref "C413") (pin "1") (pinfunction "1_1") (pintype "passive"))
      (node (ref "R413") (pin "1") (pinfunction "1_1") (pintype "passive"))
      (node (ref "U101") (pin "21") (pinfunction "21_10N_21") (pintype "bidirectional"))
    )
    (net (code "37") (name "FPGA_TRX_IRQ") (class "Default")
      (node (ref "R121") (pin "1") (pinfunction "1_1") (pintype "passive"))
      (node (ref "U101") (pin "40") (pinfunction "40_12N_40") (pintype "bidirectional"))
    )
    (net (code "38") (name "FPGA_TRX_RSTN") (class "Default")
      (node (ref "R131") (pin "2") (pinfunction "2_2") (pintype "passive"))
      (node (ref "U101") (pin "20") (pinfunction "20_9P_20") (pintype "bidirectional"))
    )
    (net (code "39") (name "GND") (class "Default")
      (node (ref "C221") (pin "2") (pinfunction "2_2") (pintype "passive"))
      (node (ref "C222") (pin "2") (pinfunction "2_2") (pintype "passive"))
      (node (ref "C311") (pin "2") (pinfunction "2_2") (pintype "passive"))
      (node (ref "C312") (pin "2") (pinfunction "2_2") (pintype "passive"))
      (node (ref "C321") (pin "2") (pinfunction "2_2") (pintype "passive"))
      (node (ref "C401") (pin "2") (pinfunction "2_2") (pintype "passive"))
      (node (ref "C411") (pin "2") (pinfunction "2_2") (pintype "passive"))
      (node (ref "C413") (pin "2") (pinfunction "2_2") (pintype "passive"))
      (node (ref "C511") (pin "2") (pinfunction "2_2") (pintype "passive"))
      (node (ref "C551") (pin "2") (pinfunction "2_2") (pintype "passive"))
      (node (ref "C552") (pin "2") (pinfunction "2_2") (pintype "passive"))
      (node (ref "C553") (pin "2") (pinfunction "2_2") (pintype "passive"))
      (node (ref "C591") (pin "2") (pinfunction "2_2") (pintype "passive"))
      (node (ref "C593") (pin "2") (pinfunction "2_2") (pintype "passive"))
      (node (ref "C595") (pin "2") (pinfunction "2_2") (pintype "passive"))
      (node (ref "C597") (pin "2") (pinfunction "2_2") (pintype "passive"))
      (node (ref "C601") (pin "2") (pinfunction "2_2") (pintype "passive"))
      (node (ref "C621") (pin "2") (pinfunction "2_2") (pintype "passive"))
      (node (ref "C711") (pin "1") (pinfunction "1_1") (pintype "passive"))
      (node (ref "D141") (pin "1") (pinfunction "BC_1") (pintype "passive"))
      (node (ref "D141") (pin "2") (pinfunction "GC_2") (pintype "passive"))
      (node (ref "D141") (pin "3") (pinfunction "RC_3") (pintype "passive"))
      (node (ref "H2311") (pin "B2,8") (pinfunction "MOUNT_B2,8") (pintype "passive"))
      (node (ref "H2321") (pin "B2,8") (pinfunction "MOUNT_B2,8") (pintype "passive"))
      (node (ref "H2331") (pin "B2,8") (pinfunction "MOUNT_B2,8") (pintype "passive"))
      (node (ref "H2341") (pin "B2,8") (pinfunction "MOUNT_B2,8") (pintype "passive"))
      (node (ref "L102") (pin "1") (pinfunction "1_1") (pintype "passive"))
      (node (ref "L401") (pin "1") (pinfunction "1_1") (pintype "passive"))
      (node (ref "L402") (pin "1") (pinfunction "1_1") (pintype "passive"))
      (node (ref "L421") (pin "1") (pinfunction "COM_1") (pintype "passive"))
      (node (ref "L422") (pin "2") (pinfunction "COM_2") (pintype "passive"))
      (node (ref "L422") (pin "5") (pinfunction "G_N_D_5") (pintype "passive"))
      (node (ref "R711") (pin "1") (pinfunction "1_1") (pintype "passive"))
      (node (ref "U301") (pin "2") (pinfunction "ADDR_2") (pintype "input"))
      (node (ref "U301") (pin "8") (pinfunction "GND_8") (pintype "passive"))
      (node (ref "U411") (pin "2") (pinfunction "GND_2") (pintype "power_in"))
      (node (ref "U511") (pin "2") (pinfunction "GND_2") (pintype "power_in"))
      (node (ref "U521") (pin "17") (pinfunction "VSS_17") (pintype "passive"))
      (node (ref "U521") (pin "4") (pinfunction "VSS_4") (pintype "passive"))
      (node (ref "U521") (pin "8") (pinfunction "VSS_8") (pintype "passive"))
      (node (ref "U581") (pin "1") (pinfunction "GROUND_1") (pintype "passive"))
      (node (ref "U581") (pin "3") (pinfunction "GROUND_3") (pintype "passive"))
      (node (ref "U581") (pin "4") (pinfunction "GROUND_4") (pintype "passive"))
      (node (ref "U581") (pin "6") (pinfunction "GROUND_6") (pintype "passive"))
      (node (ref "U611") (pin "10") (pinfunction "PGND_10") (pintype "passive"))
      (node (ref "U611") (pin "3") (pinfunction "VSS_3") (pintype "passive"))
      (node (ref "U611") (pin "6") (pinfunction "LBI_6") (pintype "input"))
      (node (ref "U611") (pin "7") (pinfunction "SYNC_7") (pintype "input"))
      (node (ref "X221") (pin "C") (pinfunction "C_C") (pintype "passive"))
      (node (ref "X221") (pin "D") (pinfunction "D_D") (pintype "passive"))
      (node (ref "X591") (pin "GND1") (pinfunction "GND_GND1") (pintype "bidirectional"))
      (node (ref "X591") (pin "GND2") (pinfunction "GND_GND2") (pintype "bidirectional"))
      (node (ref "X591") (pin "GND3") (pinfunction "GND_GND3") (pintype "bidirectional"))
      (node (ref "X591") (pin "GND4") (pinfunction "GND_GND4") (pintype "bidirectional"))
      (node (ref "X595") (pin "GND1") (pinfunction "GND_GND1") (pintype "bidirectional"))
      (node (ref "X595") (pin "GND2") (pinfunction "GND_GND2") (pintype "bidirectional"))
      (node (ref "X595") (pin "GND3") (pinfunction "GND_GND3") (pintype "bidirectional"))
      (node (ref "X595") (pin "GND4") (pinfunction "GND_GND4") (pintype "bidirectional"))
      (node (ref "X711") (pin "GND") (pinfunction "GND_GND") (pintype "passive"))
      (node (ref "X721") (pin "1") (pinfunction "1_1") (pintype "passive"))
      (node (ref "X723") (pin "8") (pinfunction "8_8") (pintype "passive"))
    )
    (net (code "40") (name "Net-(C403-Pad1)") (class "Default")
      (node (ref "C403") (pin "1") (pinfunction "1_1") (pintype "passive"))
      (node (ref "L403") (pin "2") (pinfunction "2_2") (pintype "passive"))
      (node (ref "U401") (pin "21") (pinfunction "DEVDD_21") (pintype "power_in"))
      (node (ref "U401") (pin "29") (pinfunction "DEVDD_29") (pintype "power_in"))
      (node (ref "U401") (pin "39") (pinfunction "DEVDD_39") (pintype "power_in"))
    )
    (net (code "41") (name "Net-(C403-Pad2)") (class "Default")
      (node (ref "C403") (pin "2") (pinfunction "2_2") (pintype "passive"))
      (node (ref "C406") (pin "1") (pinfunction "1_1") (pintype "passive"))
      (node (ref "L402") (pin "2") (pinfunction "2_2") (pintype "passive"))
      (node (ref "U401") (pin "20") (pinfunction "DVSS_20") (pintype "passive"))
      (node (ref "U401") (pin "23") (pinfunction "DVSS_23") (pintype "passive"))
      (node (ref "U401") (pin "24") (pinfunction "DVSS_24") (pintype "passive"))
      (node (ref "U401") (pin "32") (pinfunction "DVSS_32") (pintype "passive"))
      (node (ref "U401") (pin "38") (pinfunction "DVSS_38") (pintype "passive"))
    )
    (net (code "42") (name "Net-(C404-Pad1)") (class "Default")
      (node (ref "C404") (pin "1") (pinfunction "1_1") (pintype "passive"))
      (node (ref "L404") (pin "2") (pinfunction "2_2") (pintype "passive"))
      (node (ref "U401") (pin "15") (pinfunction "EVDD_15") (pintype "power_in"))
      (node (ref "U401") (pin "46") (pinfunction "EVDD_46") (pintype "power_in"))
    )
    (net (code "43") (name "Net-(C593-Pad1)") (class "Default")
      (node (ref "C593") (pin "1") (pinfunction "1_1") (pintype "passive"))
      (node (ref "L592") (pin "2") (pinfunction "2_2") (pintype "passive"))
      (node (ref "X591") (pin "ANT1") (pinfunction "SIGNAL_ANT1") (pintype "bidirectional"))
      (node (ref "X591") (pin "ANT2") (pinfunction "SIGNAL_ANT2") (pintype "bidirectional"))
      (node (ref "X591") (pin "ANT3") (pinfunction "SIGNAL_ANT3") (pintype "bidirectional"))
    )
    (net (code "44") (name "Net-(C597-Pad1)") (class "Default")
      (node (ref "C597") (pin "1") (pinfunction "1_1") (pintype "passive"))
      (node (ref "L596") (pin "2") (pinfunction "2_2") (pintype "passive"))
      (node (ref "X595") (pin "ANT1") (pinfunction "SIGNAL_ANT1") (pintype "bidirectional"))
      (node (ref "X595") (pin "ANT2") (pinfunction "SIGNAL_ANT2") (pintype "bidirectional"))
      (node (ref "X595") (pin "ANT3") (pinfunction "SIGNAL_ANT3") (pintype "bidirectional"))
    )
    (net (code "45") (name "Net-(C711-Pad2)") (class "Default")
      (node (ref "C711") (pin "2") (pinfunction "2_2") (pintype "passive"))
      (node (ref "R711") (pin "2") (pinfunction "2_2") (pintype "passive"))
      (node (ref "X711") (pin "JSHIELD") (pinfunction "SHIELD_JSHIELD") (pintype "passive"))
      (node (ref "X711") (pin "JSHIELD@2") (pinfunction "SHIELD_JSHIELD@2") (pintype "passive"))
      (node (ref "X711") (pin "JSHIELD@3") (pinfunction "SHIELD_JSHIELD@3") (pintype "passive"))
      (node (ref "X711") (pin "JSHIELD@4") (pinfunction "SHIELD_JSHIELD@4") (pintype "passive"))
      (node (ref "X711") (pin "JSHIELD@5") (pinfunction "SHIELD_JSHIELD@5") (pintype "passive"))
      (node (ref "X711") (pin "JSHIELD@6") (pinfunction "SHIELD_JSHIELD@6") (pintype "passive"))
    )
    (net (code "46") (name "Net-(D141-BA)") (class "Default")
      (node (ref "D141") (pin "6") (pinfunction "BA_6") (pintype "passive"))
      (node (ref "R143") (pin "1") (pinfunction "1_1") (pintype "passive"))
    )
    (net (code "47") (name "Net-(D141-GA)") (class "Default")
      (node (ref "D141") (pin "5") (pinfunction "GA_5") (pintype "passive"))
      (node (ref "R142") (pin "1") (pinfunction "1_1") (pintype "passive"))
    )
    (net (code "48") (name "Net-(D141-RA)") (class "Default")
      (node (ref "D141") (pin "4") (pinfunction "RA_4") (pintype "passive"))
      (node (ref "R141") (pin "1") (pinfunction "1_1") (pintype "passive"))
    )
    (net (code "49") (name "Net-(L421-B1)") (class "Default")
      (node (ref "L421") (pin "3") (pinfunction "B1_3") (pintype "passive"))
      (node (ref "U401") (pin "8") (pinfunction "RF09P_8") (pintype "passive"))
    )
    (net (code "50") (name "Net-(L421-B2)") (class "Default")
      (node (ref "L421") (pin "2") (pinfunction "B2_2") (pintype "passive"))
      (node (ref "U401") (pin "9") (pinfunction "RF09N_9") (pintype "passive"))
    )
    (net (code "51") (name "Net-(L422-B1)") (class "Default")
      (node (ref "L422") (pin "3") (pinfunction "B1_3") (pintype "passive"))
      (node (ref "U401") (pin "4") (pinfunction "RF24P_4") (pintype "passive"))
    )
    (net (code "52") (name "Net-(L422-B2)") (class "Default")
      (node (ref "L422") (pin "4") (pinfunction "B2_4") (pintype "passive"))
      (node (ref "U401") (pin "5") (pinfunction "RF24N_5") (pintype "passive"))
    )
    (net (code "53") (name "Net-(R721-Pad2)") (class "Default")
      (node (ref "R721") (pin "2") (pinfunction "2_2") (pintype "passive"))
      (node (ref "X721") (pin "2") (pinfunction "2_2") (pintype "passive"))
    )
    (net (code "54") (name "Net-(R722-Pad2)") (class "Default")
      (node (ref "R722") (pin "2") (pinfunction "2_2") (pintype "passive"))
      (node (ref "X721") (pin "3") (pinfunction "3_3") (pintype "passive"))
    )
    (net (code "55") (name "Net-(R723-Pad2)") (class "Default")
      (node (ref "R723") (pin "2") (pinfunction "2_2") (pintype "passive"))
      (node (ref "X721") (pin "4") (pinfunction "4_4") (pintype "passive"))
    )
    (net (code "56") (name "Net-(R724-Pad2)") (class "Default")
      (node (ref "R724") (pin "2") (pinfunction "2_2") (pintype "passive"))
      (node (ref "X721") (pin "5") (pinfunction "5_5") (pintype "passive"))
    )
    (net (code "57") (name "Net-(R733-Pad2)") (class "Default")
      (node (ref "R733") (pin "2") (pinfunction "2_2") (pintype "passive"))
      (node (ref "X723") (pin "3") (pinfunction "3_3") (pintype "passive"))
    )
    (net (code "58") (name "Net-(R734-Pad2)") (class "Default")
      (node (ref "R734") (pin "2") (pinfunction "2_2") (pintype "passive"))
      (node (ref "X723") (pin "4") (pinfunction "4_4") (pintype "passive"))
    )
    (net (code "59") (name "Net-(R735-Pad2)") (class "Default")
      (node (ref "R735") (pin "2") (pinfunction "2_2") (pintype "passive"))
      (node (ref "X723") (pin "5") (pinfunction "5_5") (pintype "passive"))
    )
    (net (code "60") (name "Net-(R736-Pad2)") (class "Default")
      (node (ref "R736") (pin "2") (pinfunction "2_2") (pintype "passive"))
      (node (ref "X723") (pin "6") (pinfunction "6_6") (pintype "passive"))
    )
    (net (code "61") (name "Net-(U101-07_6N)") (class "Default")
      (node (ref "R151") (pin "2") (pinfunction "2_2") (pintype "passive"))
      (node (ref "U101") (pin "7") (pinfunction "07_6N_7") (pintype "bidirectional"))
    )
    (net (code "62") (name "Net-(U101-09_6P)") (class "Default")
      (node (ref "R141") (pin "2") (pinfunction "2_2") (pintype "passive"))
      (node (ref "U101") (pin "9") (pinfunction "09_6P_9") (pintype "bidirectional"))
    )
    (net (code "63") (name "Net-(U101-10_7P)") (class "Default")
      (node (ref "R142") (pin "2") (pinfunction "2_2") (pintype "passive"))
      (node (ref "U101") (pin "10") (pinfunction "10_7P_10") (pintype "bidirectional"))
    )
    (net (code "64") (name "Net-(U101-11_3N)") (class "Default")
      (node (ref "R143") (pin "2") (pinfunction "2_2") (pintype "passive"))
      (node (ref "U101") (pin "11") (pinfunction "11_3N_11") (pintype "bidirectional"))
    )
    (net (code "65") (name "Net-(U101-13_6N)") (class "Default")
      (node (ref "R152") (pin "2") (pinfunction "2_2") (pintype "passive"))
      (node (ref "U101") (pin "13") (pinfunction "13_6N_13") (pintype "bidirectional"))
    )
    (net (code "66") (name "Net-(U401-AVDD0)") (class "Default")
      (node (ref "C407") (pin "2") (pinfunction "2_2") (pintype "passive"))
      (node (ref "U401") (pin "14") (pinfunction "AVDD0_14") (pintype "passive"))
    )
    (net (code "67") (name "Net-(U401-AVDD1)") (class "Default")
      (node (ref "C408") (pin "2") (pinfunction "2_2") (pintype "passive"))
      (node (ref "U401") (pin "47") (pinfunction "AVDD1_47") (pintype "passive"))
    )
    (net (code "68") (name "Net-(U401-CLKO)") (class "Default")
      (node (ref "R413") (pin "2") (pinfunction "2_2") (pintype "passive"))
      (node (ref "U401") (pin "22") (pinfunction "CLKO_22") (pintype "output"))
    )
    (net (code "69") (name "Net-(U401-DVDD)") (class "Default")
      (node (ref "C406") (pin "2") (pinfunction "2_2") (pintype "passive"))
      (node (ref "U401") (pin "37") (pinfunction "DVDD_37") (pintype "passive"))
    )
    (net (code "70") (name "Net-(U401-TCXO)") (class "Default")
      (node (ref "C412") (pin "2") (pinfunction "2_2") (pintype "passive"))
      (node (ref "U401") (pin "17") (pinfunction "TCXO_17") (pintype "input"))
    )
    (net (code "71") (name "Net-(U401-XTAL2)") (class "Default")
      (node (ref "C404") (pin "2") (pinfunction "2_2") (pintype "passive"))
      (node (ref "C407") (pin "1") (pinfunction "1_1") (pintype "passive"))
      (node (ref "C408") (pin "1") (pinfunction "1_1") (pintype "passive"))
      (node (ref "L401") (pin "2") (pinfunction "2_2") (pintype "passive"))
      (node (ref "U401") (pin "10") (pinfunction "AVSS_10") (pintype "passive"))
      (node (ref "U401") (pin "16") (pinfunction "AVSS_16") (pintype "passive"))
      (node (ref "U401") (pin "18") (pinfunction "XTAL2_18") (pintype "passive"))
      (node (ref "U401") (pin "19") (pinfunction "AVSS_19") (pintype "passive"))
      (node (ref "U401") (pin "3") (pinfunction "AVSS_3") (pintype "passive"))
      (node (ref "U401") (pin "45") (pinfunction "AVSS_45") (pintype "passive"))
      (node (ref "U401") (pin "48") (pinfunction "AVSS_48") (pintype "passive"))
      (node (ref "U401") (pin "49") (pinfunction "AVSS_49") (pintype "passive"))
      (node (ref "U401") (pin "6") (pinfunction "AVSS_6") (pintype "passive"))
      (node (ref "U401") (pin "7") (pinfunction "AVSS_7") (pintype "passive"))
    )
    (net (code "72") (name "Net-(U411-OUT)") (class "Default")
      (node (ref "C412") (pin "1") (pinfunction "1_1") (pintype "passive"))
      (node (ref "U411") (pin "3") (pinfunction "OUT_3") (pintype "output"))
    )
    (net (code "73") (name "Net-(U511-RF1)") (class "Default")
      (node (ref "C531") (pin "2") (pinfunction "2_2") (pintype "passive"))
      (node (ref "U511") (pin "1") (pinfunction "RF1_1") (pintype "passive"))
    )
    (net (code "74") (name "Net-(U511-RF2)") (class "Default")
      (node (ref "C532") (pin "2") (pinfunction "2_2") (pintype "passive"))
      (node (ref "U511") (pin "3") (pinfunction "RF2_3") (pintype "passive"))
    )
    (net (code "75") (name "Net-(U511-RFC)") (class "Default")
      (node (ref "C521") (pin "1") (pinfunction "1_1") (pintype "passive"))
      (node (ref "U511") (pin "5") (pinfunction "RFC_5") (pintype "passive"))
    )
    (net (code "76") (name "Net-(U521-IND)") (class "Default")
      (node (ref "L521") (pin "1") (pinfunction "1_1") (pintype "passive"))
      (node (ref "U521") (pin "10") (pinfunction "IND_10") (pintype "passive"))
    )
    (net (code "77") (name "Net-(U581-OUT)") (class "Default")
      (node (ref "C591") (pin "1") (pinfunction "1_1") (pintype "passive"))
      (node (ref "L592") (pin "1") (pinfunction "1_1") (pintype "passive"))
      (node (ref "U581") (pin "5") (pinfunction "OUT_5") (pintype "passive"))
    )
    (net (code "78") (name "Net-(U611-SW)") (class "Default")
      (node (ref "L611") (pin "2") (pinfunction "2_2") (pintype "passive"))
      (node (ref "U611") (pin "9") (pinfunction "SW_9") (pintype "passive"))
    )
    (net (code "79") (name "Net-(X711-J_VUSB)") (class "Default")
      (node (ref "PF711") (pin "2") (pinfunction "2_2") (pintype "passive"))
      (node (ref "X711") (pin "VBUS") (pinfunction "J_VUSB_VBUS") (pintype "power_in"))
    )
    (net (code "80") (name "ROT_I_R") (class "Default")
      (node (ref "C221") (pin "1") (pinfunction "1_1") (pintype "passive"))
      (node (ref "R151") (pin "1") (pinfunction "1_1") (pintype "passive"))
      (node (ref "X221") (pin "A") (pinfunction "A_A") (pintype "passive"))
    )
    (net (code "81") (name "ROT_Q_R") (class "Default")
      (node (ref "C222") (pin "1") (pinfunction "1_1") (pintype "passive"))
      (node (ref "R152") (pin "1") (pinfunction "1_1") (pintype "passive"))
      (node (ref "X221") (pin "B") (pinfunction "B_B") (pintype "passive"))
    )
    (net (code "82") (name "TRX_FEA09") (class "Default")
      (node (ref "U401") (pin "11") (pinfunction "FEA09_11") (pintype "output"))
      (node (ref "U511") (pin "4") (pinfunction "CTRL_4") (pintype "input"))
      (node (ref "U521") (pin "2") (pinfunction "TXEN_2") (pintype "input"))
    )
    (net (code "83") (name "TRX_FEA24") (class "Default")
      (node (ref "U401") (pin "1") (pinfunction "FEA24_1") (pintype "output"))
    )
    (net (code "84") (name "TRX_FEB09") (class "Default")
      (node (ref "U401") (pin "12") (pinfunction "FEB09_12") (pintype "output"))
      (node (ref "U521") (pin "1") (pinfunction "RXEN_1") (pintype "input"))
    )
    (net (code "85") (name "TRX_FEB24") (class "Default")
      (node (ref "U401") (pin "2") (pinfunction "FEB24_2") (pintype "output"))
    )
    (net (code "86") (name "TRX_IRQ") (class "Default")
      (node (ref "R121") (pin "2") (pinfunction "2_2") (pintype "passive"))
      (node (ref "U401") (pin "40") (pinfunction "IRQ_40") (pintype "output"))
    )
    (net (code "87") (name "TRX_MISO") (class "Default")
      (node (ref "R114") (pin "2") (pinfunction "2_2") (pintype "passive"))
      (node (ref "U401") (pin "44") (pinfunction "MISO_44") (pintype "output"))
    )
    (net (code "88") (name "TRX_MOSI") (class "Default")
      (node (ref "R113") (pin "2") (pinfunction "2_2") (pintype "passive"))
      (node (ref "U401") (pin "43") (pinfunction "MOSI_43") (pintype "input"))
    )
    (net (code "89") (name "TRX_RF09") (class "Default")
      (node (ref "C521") (pin "2") (pinfunction "2_2") (pintype "passive"))
      (node (ref "L421") (pin "4") (pinfunction "UB_4") (pintype "passive"))
    )
    (net (code "90") (name "TRX_RF24") (class "Default")
      (node (ref "C595") (pin "1") (pinfunction "1_1") (pintype "passive"))
      (node (ref "L422") (pin "1") (pinfunction "UB_1") (pintype "passive"))
      (node (ref "L596") (pin "1") (pinfunction "1_1") (pintype "passive"))
    )
    (net (code "91") (name "TRX_RSTN") (class "Default")
      (node (ref "R131") (pin "1") (pinfunction "1_1") (pintype "passive"))
      (node (ref "U401") (pin "13") (pinfunction "RSTN_13") (pintype "input"))
    )
    (net (code "92") (name "TRX_RXCLK_N") (class "Default")
      (node (ref "U101") (pin "48") (pinfunction "48_14N_48") (pintype "bidirectional"))
      (node (ref "U401") (pin "33") (pinfunction "RXCLKN_33") (pintype "output"))
    )
    (net (code "93") (name "TRX_RXCLK_P") (class "Default")
      (node (ref "U101") (pin "47") (pinfunction "47_14P_47") (pintype "bidirectional"))
      (node (ref "U401") (pin "34") (pinfunction "RXCLKP_34") (pintype "output"))
    )
    (net (code "94") (name "TRX_RXD09_N") (class "Default")
      (node (ref "U101") (pin "37") (pinfunction "37_11N_37") (pintype "bidirectional"))
      (node (ref "U401") (pin "30") (pinfunction "RXD09N_30") (pintype "output"))
    )
    (net (code "95") (name "TRX_RXD09_P") (class "Default")
      (node (ref "U101") (pin "38") (pinfunction "38_11P_38") (pintype "bidirectional"))
      (node (ref "U401") (pin "31") (pinfunction "RXD09P_31") (pintype "output"))
    )
    (net (code "96") (name "TRX_RXD24_N") (class "Default")
      (node (ref "U101") (pin "1") (pinfunction "01_8N_1") (pintype "bidirectional"))
      (node (ref "U401") (pin "35") (pinfunction "RXD24N_35") (pintype "output"))
    )
    (net (code "97") (name "TRX_RXD24_P") (class "Default")
      (node (ref "U101") (pin "2") (pinfunction "02_8P_2") (pintype "bidirectional"))
      (node (ref "U401") (pin "36") (pinfunction "RXD24P_36") (pintype "output"))
    )
    (net (code "98") (name "TRX_SCLK") (class "Default")
      (node (ref "R111") (pin "2") (pinfunction "2_2") (pintype "passive"))
      (node (ref "U401") (pin "41") (pinfunction "SCLK_41") (pintype "input"))
    )
    (net (code "99") (name "TRX_SELN") (class "Default")
      (node (ref "R112") (pin "2") (pinfunction "2_2") (pintype "passive"))
      (node (ref "U401") (pin "42") (pinfunction "SELN_42") (pintype "input"))
    )
    (net (code "100") (name "TRX_TXCLK_N") (class "Default")
      (node (ref "U101") (pin "19") (pinfunction "19_12N_19") (pintype "bidirectional"))
      (node (ref "U401") (pin "25") (pinfunction "TXCLKN_25") (pintype "input"))
    )
    (net (code "101") (name "TRX_TXCLK_P") (class "Default")
      (node (ref "U101") (pin "18") (pinfunction "18_12P_18") (pintype "bidirectional"))
      (node (ref "U401") (pin "26") (pinfunction "TXCLKP_26") (pintype "input"))
    )
    (net (code "102") (name "TRX_TXD_N") (class "Default")
      (node (ref "U101") (pin "34") (pinfunction "34_6N_34") (pintype "bidirectional"))
      (node (ref "U401") (pin "27") (pinfunction "TXDN_27") (pintype "input"))
    )
    (net (code "103") (name "TRX_TXD_P") (class "Default")
      (node (ref "U101") (pin "35") (pinfunction "35_6P_35") (pintype "bidirectional"))
      (node (ref "U401") (pin "28") (pinfunction "TXDP_28") (pintype "input"))
    )
    (net (code "104") (name "VCCA") (class "Default")
      (node (ref "C101") (pin "2") (pinfunction "2_2") (pintype "passive"))
      (node (ref "L101") (pin "2") (pinfunction "2_2") (pintype "passive"))
      (node (ref "U101") (pin "24") (pinfunction "24_VU_24") (pintype "power_in"))
    )
    (net (code "105") (name "VCTCXO_VC") (class "Default")
      (node (ref "C321") (pin "1") (pinfunction "1_1") (pintype "passive"))
      (node (ref "R321") (pin "2") (pinfunction "2_2") (pintype "passive"))
      (node (ref "U411") (pin "1") (pinfunction "VC_1") (pintype "input"))
    )
    (net (code "106") (name "VSSA") (class "Default")
      (node (ref "C101") (pin "1") (pinfunction "1_1") (pintype "passive"))
      (node (ref "L102") (pin "2") (pinfunction "2_2") (pintype "passive"))
      (node (ref "U101") (pin "25") (pinfunction "25_GND_25") (pintype "passive"))
    )
    (net (code "107") (name "unconnected-(U521-DC-Pad6)") (class "Default")
      (node (ref "U521") (pin "6") (pinfunction "DC_6") (pintype "no_connect"))
    )
    (net (code "108") (name "unconnected-(U521-DC-Pad11)") (class "Default")
      (node (ref "U521") (pin "11") (pinfunction "DC_11") (pintype "no_connect"))
    )
    (net (code "109") (name "unconnected-(U521-DC-Pad12)") (class "Default")
      (node (ref "U521") (pin "12") (pinfunction "DC_12") (pintype "no_connect"))
    )
    (net (code "110") (name "unconnected-(U611-LBO-Pad2)") (class "Default")
      (node (ref "U611") (pin "2") (pinfunction "LBO_2") (pintype "output"))
    )
    (net (code "111") (name "unconnected-(U611-PG-Pad4)") (class "Default")
      (node (ref "U611") (pin "4") (pinfunction "PG_4") (pintype "output"))
    )
    (net (code "112") (name "unconnected-(X221-PadE)") (class "Default")
      (node (ref "X221") (pin "E") (pinfunction "E_E") (pintype "passive"))
    )
    (net (code "113") (name "unconnected-(X711-J_D+-PadD+)") (class "Default")
      (node (ref "X711") (pin "D+") (pinfunction "J_D+_D+") (pintype "bidirectional"))
    )
    (net (code "114") (name "unconnected-(X711-J_D--PadD-)") (class "Default")
      (node (ref "X711") (pin "D-") (pinfunction "J_D-_D-") (pintype "bidirectional"))
    )
    (net (code "115") (name "unconnected-(X711-J_ID-PadID)") (class "Default")
      (node (ref "X711") (pin "ID") (pinfunction "J_ID_ID") (pintype "bidirectional"))
    )
  )
)
